# PwrAndBias.net
KiCad netlist of a schematic drawn in Altium Designer
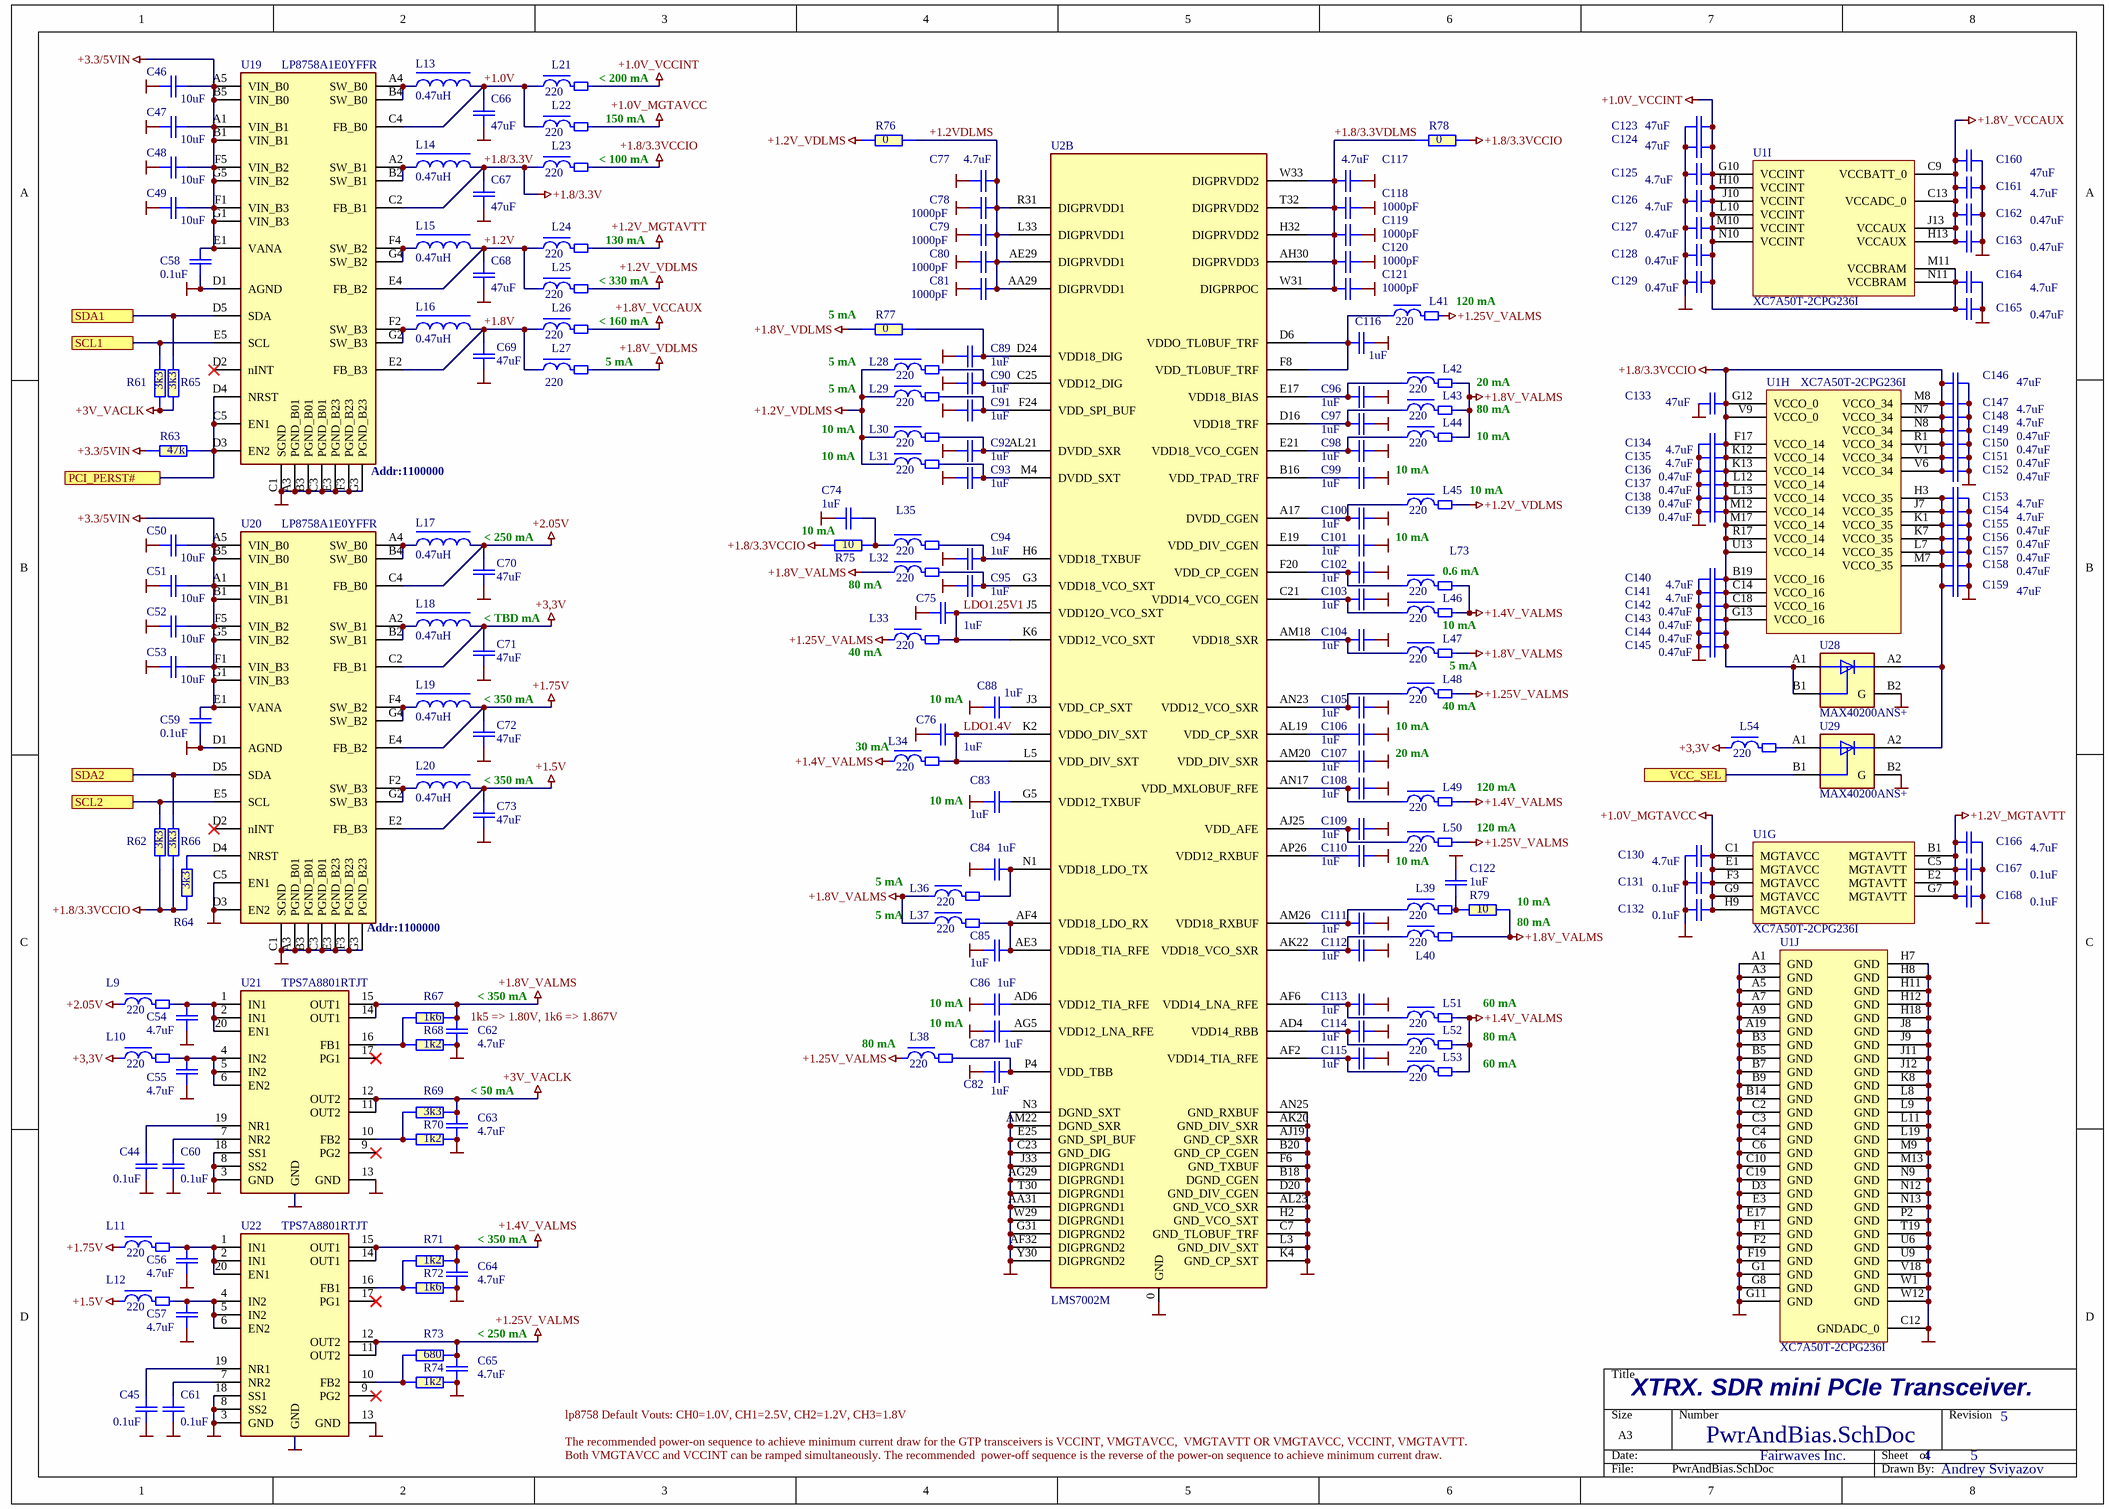
[diagram p0: PwrAndBias.SchDoc]

(export (version "E")
  (design (tool "Eeschema 10.0.6"))
  (components
    (comp (ref "C44")
      (value "0.1uF")
      (footprint "C0402-cirq")
      (description "Capacitor")
      (fields (field (name "MANUFACTURER") "Any") (field (name "TOLERANCE") "20%"))
      (libsource (lib "Capacitors") (part "C0402"))
    )
    (comp (ref "C45")
      (value "0.1uF")
      (footprint "C0402-cirq")
      (description "Capacitor")
      (fields (field (name "MANUFACTURER") "Any") (field (name "TOLERANCE") "20%"))
      (libsource (lib "Capacitors") (part "C0402"))
    )
    (comp (ref "C46")
      (value "10uF")
      (footprint "C0603-Phillips")
      (description "Capacitor")
      (fields (field (name "MANUFACTURER") "Any") (field (name "TOLERANCE") "20%"))
      (libsource (lib "Capacitors") (part "C0603"))
    )
    (comp (ref "C47")
      (value "10uF")
      (footprint "C0603-Phillips")
      (description "Capacitor")
      (fields (field (name "MANUFACTURER") "Any") (field (name "TOLERANCE") "20%"))
      (libsource (lib "Capacitors") (part "C0603"))
    )
    (comp (ref "C48")
      (value "10uF")
      (footprint "C0603-Phillips")
      (description "Capacitor")
      (fields (field (name "MANUFACTURER") "Any") (field (name "TOLERANCE") "20%"))
      (libsource (lib "Capacitors") (part "C0603"))
    )
    (comp (ref "C49")
      (value "10uF")
      (footprint "C0603-Phillips")
      (description "Capacitor")
      (fields (field (name "MANUFACTURER") "Any") (field (name "TOLERANCE") "20%"))
      (libsource (lib "Capacitors") (part "C0603"))
    )
    (comp (ref "C50")
      (value "10uF")
      (footprint "C0603-Phillips")
      (description "Capacitor")
      (fields (field (name "MANUFACTURER") "Any") (field (name "TOLERANCE") "20%"))
      (libsource (lib "Capacitors") (part "C0603"))
    )
    (comp (ref "C51")
      (value "10uF")
      (footprint "C0603-Phillips")
      (description "Capacitor")
      (fields (field (name "MANUFACTURER") "Any") (field (name "TOLERANCE") "20%"))
      (libsource (lib "Capacitors") (part "C0603"))
    )
    (comp (ref "C52")
      (value "10uF")
      (footprint "C0603-Phillips")
      (description "Capacitor")
      (fields (field (name "MANUFACTURER") "Any") (field (name "TOLERANCE") "20%"))
      (libsource (lib "Capacitors") (part "C0603"))
    )
    (comp (ref "C53")
      (value "10uF")
      (footprint "C0603-Phillips")
      (description "Capacitor")
      (fields (field (name "MANUFACTURER") "Any") (field (name "TOLERANCE") "20%"))
      (libsource (lib "Capacitors") (part "C0603"))
    )
    (comp (ref "C54")
      (value "4.7uF")
      (footprint "C0402-cirq")
      (description "Capacitor")
      (fields (field (name "MANUFACTURER") "Any") (field (name "TOLERANCE") "20%"))
      (libsource (lib "Capacitors") (part "C0402"))
    )
    (comp (ref "C55")
      (value "4.7uF")
      (footprint "C0402-cirq")
      (description "Capacitor")
      (fields (field (name "MANUFACTURER") "Any") (field (name "TOLERANCE") "20%"))
      (libsource (lib "Capacitors") (part "C0402"))
    )
    (comp (ref "C56")
      (value "4.7uF")
      (footprint "C0402-cirq")
      (description "Capacitor")
      (fields (field (name "MANUFACTURER") "Any") (field (name "TOLERANCE") "20%"))
      (libsource (lib "Capacitors") (part "C0402"))
    )
    (comp (ref "C57")
      (value "4.7uF")
      (footprint "C0402-cirq")
      (description "Capacitor")
      (fields (field (name "MANUFACTURER") "Any") (field (name "TOLERANCE") "20%"))
      (libsource (lib "Capacitors") (part "C0402"))
    )
    (comp (ref "C58")
      (value "0.1uF")
      (footprint "C0402-cirq")
      (description "Capacitor")
      (fields (field (name "MANUFACTURER") "Any") (field (name "TOLERANCE") "20%"))
      (libsource (lib "Capacitors") (part "C0402"))
    )
    (comp (ref "C59")
      (value "0.1uF")
      (footprint "C0402-cirq")
      (description "Capacitor")
      (fields (field (name "MANUFACTURER") "Any") (field (name "TOLERANCE") "20%"))
      (libsource (lib "Capacitors") (part "C0402"))
    )
    (comp (ref "C60")
      (value "0.1uF")
      (footprint "C0402-cirq")
      (description "Capacitor")
      (fields (field (name "MANUFACTURER") "Any") (field (name "TOLERANCE") "20%"))
      (libsource (lib "Capacitors") (part "C0402"))
    )
    (comp (ref "C61")
      (value "0.1uF")
      (footprint "C0402-cirq")
      (description "Capacitor")
      (fields (field (name "MANUFACTURER") "Any") (field (name "TOLERANCE") "20%"))
      (libsource (lib "Capacitors") (part "C0402"))
    )
    (comp (ref "C62")
      (value "4.7uF")
      (footprint "C0402-cirq")
      (description "Capacitor")
      (fields (field (name "MANUFACTURER") "Any") (field (name "TOLERANCE") "20%"))
      (libsource (lib "Capacitors") (part "C0402"))
    )
    (comp (ref "C63")
      (value "4.7uF")
      (footprint "C0402-cirq")
      (description "Capacitor")
      (fields (field (name "MANUFACTURER") "Any") (field (name "TOLERANCE") "20%"))
      (libsource (lib "Capacitors") (part "C0402"))
    )
    (comp (ref "C64")
      (value "4.7uF")
      (footprint "C0402-cirq")
      (description "Capacitor")
      (fields (field (name "MANUFACTURER") "Any") (field (name "TOLERANCE") "20%"))
      (libsource (lib "Capacitors") (part "C0402"))
    )
    (comp (ref "C65")
      (value "4.7uF")
      (footprint "C0402-cirq")
      (description "Capacitor")
      (fields (field (name "MANUFACTURER") "Any") (field (name "TOLERANCE") "20%"))
      (libsource (lib "Capacitors") (part "C0402"))
    )
    (comp (ref "C66")
      (value "47uF")
      (footprint "C0603 tall")
      (description "Capacitor")
      (fields (field (name "MANUFACTURER") "MuRata") (field (name "TOLERANCE") "20%"))
      (libsource (lib "Andy") (part "C0603-TALL"))
    )
    (comp (ref "C67")
      (value "47uF")
      (footprint "C0603 tall")
      (description "Capacitor")
      (fields (field (name "MANUFACTURER") "MuRata") (field (name "TOLERANCE") "20%"))
      (libsource (lib "Andy") (part "C0603-TALL"))
    )
    (comp (ref "C68")
      (value "47uF")
      (footprint "C0603 tall")
      (description "Capacitor")
      (fields (field (name "MANUFACTURER") "MuRata") (field (name "TOLERANCE") "20%"))
      (libsource (lib "Andy") (part "C0603-TALL"))
    )
    (comp (ref "C69")
      (value "47uF")
      (footprint "C0603 tall")
      (description "Capacitor")
      (fields (field (name "MANUFACTURER") "MuRata") (field (name "TOLERANCE") "20%"))
      (libsource (lib "Andy") (part "C0603-TALL"))
    )
    (comp (ref "C70")
      (value "47uF")
      (footprint "C0603 tall")
      (description "Capacitor")
      (fields (field (name "MANUFACTURER") "MuRata") (field (name "TOLERANCE") "20%"))
      (libsource (lib "Andy") (part "C0603-TALL"))
    )
    (comp (ref "C71")
      (value "47uF")
      (footprint "C0603 tall")
      (description "Capacitor")
      (fields (field (name "MANUFACTURER") "MuRata") (field (name "TOLERANCE") "20%"))
      (libsource (lib "Andy") (part "C0603-TALL"))
    )
    (comp (ref "C72")
      (value "47uF")
      (footprint "C0603 tall")
      (description "Capacitor")
      (fields (field (name "MANUFACTURER") "MuRata") (field (name "TOLERANCE") "20%"))
      (libsource (lib "Andy") (part "C0603-TALL"))
    )
    (comp (ref "C73")
      (value "47uF")
      (footprint "C0603 tall")
      (description "Capacitor")
      (fields (field (name "MANUFACTURER") "MuRata") (field (name "TOLERANCE") "20%"))
      (libsource (lib "Andy") (part "C0603-TALL"))
    )
    (comp (ref "C74")
      (value "1uF")
      (footprint "C0402-cirq")
      (description "Capacitor")
      (fields (field (name "MANUFACTURER") "Any") (field (name "TOLERANCE") "20%"))
      (libsource (lib "Capacitors") (part "C0402"))
    )
    (comp (ref "C75")
      (value "1uF")
      (footprint "C0402-cirq")
      (description "Capacitor")
      (fields (field (name "MANUFACTURER") "Any") (field (name "TOLERANCE") "20%"))
      (libsource (lib "Capacitors") (part "C0402"))
    )
    (comp (ref "C76")
      (value "1uF")
      (footprint "C0402-cirq")
      (description "Capacitor")
      (fields (field (name "MANUFACTURER") "Any") (field (name "TOLERANCE") "20%"))
      (libsource (lib "Capacitors") (part "C0402"))
    )
    (comp (ref "C77")
      (value "4.7uF")
      (footprint "C0402-cirq")
      (description "Capacitor")
      (fields (field (name "MANUFACTURER") "Any") (field (name "TOLERANCE") "20%"))
      (libsource (lib "Capacitors") (part "C0402"))
    )
    (comp (ref "C78")
      (value "1000pF")
      (footprint "C0402-cirq")
      (description "Capacitor")
      (fields (field (name "MANUFACTURER") "Any") (field (name "TOLERANCE") "10%"))
      (libsource (lib "Capacitors") (part "C0402"))
    )
    (comp (ref "C79")
      (value "1000pF")
      (footprint "C0402-cirq")
      (description "Capacitor")
      (fields (field (name "MANUFACTURER") "Any") (field (name "TOLERANCE") "10%"))
      (libsource (lib "Capacitors") (part "C0402"))
    )
    (comp (ref "C80")
      (value "1000pF")
      (footprint "C0402-cirq")
      (description "Capacitor")
      (fields (field (name "MANUFACTURER") "Any") (field (name "TOLERANCE") "10%"))
      (libsource (lib "Capacitors") (part "C0402"))
    )
    (comp (ref "C81")
      (value "1000pF")
      (footprint "C0402-cirq")
      (description "Capacitor")
      (fields (field (name "MANUFACTURER") "Any") (field (name "TOLERANCE") "10%"))
      (libsource (lib "Capacitors") (part "C0402"))
    )
    (comp (ref "C82")
      (value "1uF")
      (footprint "C0402-cirq")
      (description "Capacitor")
      (fields (field (name "MANUFACTURER") "Any") (field (name "TOLERANCE") "20%"))
      (libsource (lib "Capacitors") (part "C0402"))
    )
    (comp (ref "C83")
      (value "1uF")
      (footprint "C0402-cirq")
      (description "Capacitor")
      (fields (field (name "MANUFACTURER") "Any") (field (name "TOLERANCE") "20%"))
      (libsource (lib "Capacitors") (part "C0402"))
    )
    (comp (ref "C84")
      (value "1uF")
      (footprint "C0402-cirq")
      (description "Capacitor")
      (fields (field (name "MANUFACTURER") "Any") (field (name "TOLERANCE") "20%"))
      (libsource (lib "Capacitors") (part "C0402"))
    )
    (comp (ref "C85")
      (value "1uF")
      (footprint "C0402-cirq")
      (description "Capacitor")
      (fields (field (name "MANUFACTURER") "Any") (field (name "TOLERANCE") "20%"))
      (libsource (lib "Capacitors") (part "C0402"))
    )
    (comp (ref "C86")
      (value "1uF")
      (footprint "C0402-cirq")
      (description "Capacitor")
      (fields (field (name "MANUFACTURER") "Any") (field (name "TOLERANCE") "20%"))
      (libsource (lib "Capacitors") (part "C0402"))
    )
    (comp (ref "C87")
      (value "1uF")
      (footprint "C0402-cirq")
      (description "Capacitor")
      (fields (field (name "MANUFACTURER") "Any") (field (name "TOLERANCE") "20%"))
      (libsource (lib "Capacitors") (part "C0402"))
    )
    (comp (ref "C88")
      (value "1uF")
      (footprint "C0402-cirq")
      (description "Capacitor")
      (fields (field (name "MANUFACTURER") "Any") (field (name "TOLERANCE") "20%"))
      (libsource (lib "Capacitors") (part "C0402"))
    )
    (comp (ref "C89")
      (value "1uF")
      (footprint "C0402-cirq")
      (description "Capacitor")
      (fields (field (name "MANUFACTURER") "Any") (field (name "TOLERANCE") "20%"))
      (libsource (lib "Capacitors") (part "C0402"))
    )
    (comp (ref "C90")
      (value "1uF")
      (footprint "C0402-cirq")
      (description "Capacitor")
      (fields (field (name "MANUFACTURER") "Any") (field (name "TOLERANCE") "20%"))
      (libsource (lib "Capacitors") (part "C0402"))
    )
    (comp (ref "C91")
      (value "1uF")
      (footprint "C0402-cirq")
      (description "Capacitor")
      (fields (field (name "MANUFACTURER") "Any") (field (name "TOLERANCE") "20%"))
      (libsource (lib "Capacitors") (part "C0402"))
    )
    (comp (ref "C92")
      (value "1uF")
      (footprint "C0402-cirq")
      (description "Capacitor")
      (fields (field (name "MANUFACTURER") "Any") (field (name "TOLERANCE") "20%"))
      (libsource (lib "Capacitors") (part "C0402"))
    )
    (comp (ref "C93")
      (value "1uF")
      (footprint "C0402-cirq")
      (description "Capacitor")
      (fields (field (name "MANUFACTURER") "Any") (field (name "TOLERANCE") "20%"))
      (libsource (lib "Capacitors") (part "C0402"))
    )
    (comp (ref "C94")
      (value "1uF")
      (footprint "C0402-cirq")
      (description "Capacitor")
      (fields (field (name "MANUFACTURER") "Any") (field (name "TOLERANCE") "20%"))
      (libsource (lib "Capacitors") (part "C0402"))
    )
    (comp (ref "C95")
      (value "1uF")
      (footprint "C0402-cirq")
      (description "Capacitor")
      (fields (field (name "MANUFACTURER") "Any") (field (name "TOLERANCE") "20%"))
      (libsource (lib "Capacitors") (part "C0402"))
    )
    (comp (ref "C96")
      (value "1uF")
      (footprint "C0402-cirq")
      (description "Capacitor")
      (fields (field (name "MANUFACTURER") "Any") (field (name "TOLERANCE") "20%"))
      (libsource (lib "Capacitors") (part "C0402"))
    )
    (comp (ref "C97")
      (value "1uF")
      (footprint "C0402-cirq")
      (description "Capacitor")
      (fields (field (name "MANUFACTURER") "Any") (field (name "TOLERANCE") "20%"))
      (libsource (lib "Capacitors") (part "C0402"))
    )
    (comp (ref "C98")
      (value "1uF")
      (footprint "C0402-cirq")
      (description "Capacitor")
      (fields (field (name "MANUFACTURER") "Any") (field (name "TOLERANCE") "20%"))
      (libsource (lib "Capacitors") (part "C0402"))
    )
    (comp (ref "C99")
      (value "1uF")
      (footprint "C0402-cirq")
      (description "Capacitor")
      (fields (field (name "MANUFACTURER") "Any") (field (name "TOLERANCE") "20%"))
      (libsource (lib "Capacitors") (part "C0402"))
    )
    (comp (ref "C100")
      (value "1uF")
      (footprint "C0402-cirq")
      (description "Capacitor")
      (fields (field (name "MANUFACTURER") "Any") (field (name "TOLERANCE") "20%"))
      (libsource (lib "Capacitors") (part "C0402"))
    )
    (comp (ref "C101")
      (value "1uF")
      (footprint "C0402-cirq")
      (description "Capacitor")
      (fields (field (name "MANUFACTURER") "Any") (field (name "TOLERANCE") "20%"))
      (libsource (lib "Capacitors") (part "C0402"))
    )
    (comp (ref "C102")
      (value "1uF")
      (footprint "C0402-cirq")
      (description "Capacitor")
      (fields (field (name "MANUFACTURER") "Any") (field (name "TOLERANCE") "20%"))
      (libsource (lib "Capacitors") (part "C0402"))
    )
    (comp (ref "C103")
      (value "1uF")
      (footprint "C0402-cirq")
      (description "Capacitor")
      (fields (field (name "MANUFACTURER") "Any") (field (name "TOLERANCE") "20%"))
      (libsource (lib "Capacitors") (part "C0402"))
    )
    (comp (ref "C104")
      (value "1uF")
      (footprint "C0402-cirq")
      (description "Capacitor")
      (fields (field (name "MANUFACTURER") "Any") (field (name "TOLERANCE") "20%"))
      (libsource (lib "Capacitors") (part "C0402"))
    )
    (comp (ref "C105")
      (value "1uF")
      (footprint "C0402-cirq")
      (description "Capacitor")
      (fields (field (name "MANUFACTURER") "Any") (field (name "TOLERANCE") "20%"))
      (libsource (lib "Capacitors") (part "C0402"))
    )
    (comp (ref "C106")
      (value "1uF")
      (footprint "C0402-cirq")
      (description "Capacitor")
      (fields (field (name "MANUFACTURER") "Any") (field (name "TOLERANCE") "20%"))
      (libsource (lib "Capacitors") (part "C0402"))
    )
    (comp (ref "C107")
      (value "1uF")
      (footprint "C0402-cirq")
      (description "Capacitor")
      (fields (field (name "MANUFACTURER") "Any") (field (name "TOLERANCE") "20%"))
      (libsource (lib "Capacitors") (part "C0402"))
    )
    (comp (ref "C108")
      (value "1uF")
      (footprint "C0402-cirq")
      (description "Capacitor")
      (fields (field (name "MANUFACTURER") "Any") (field (name "TOLERANCE") "20%"))
      (libsource (lib "Capacitors") (part "C0402"))
    )
    (comp (ref "C109")
      (value "1uF")
      (footprint "C0402-cirq")
      (description "Capacitor")
      (fields (field (name "MANUFACTURER") "Any") (field (name "TOLERANCE") "20%"))
      (libsource (lib "Capacitors") (part "C0402"))
    )
    (comp (ref "C110")
      (value "1uF")
      (footprint "C0402-cirq")
      (description "Capacitor")
      (fields (field (name "MANUFACTURER") "Any") (field (name "TOLERANCE") "20%"))
      (libsource (lib "Capacitors") (part "C0402"))
    )
    (comp (ref "C111")
      (value "1uF")
      (footprint "C0402-cirq")
      (description "Capacitor")
      (fields (field (name "MANUFACTURER") "Any") (field (name "TOLERANCE") "20%"))
      (libsource (lib "Capacitors") (part "C0402"))
    )
    (comp (ref "C112")
      (value "1uF")
      (footprint "C0402-cirq")
      (description "Capacitor")
      (fields (field (name "MANUFACTURER") "Any") (field (name "TOLERANCE") "20%"))
      (libsource (lib "Capacitors") (part "C0402"))
    )
    (comp (ref "C113")
      (value "1uF")
      (footprint "C0402-cirq")
      (description "Capacitor")
      (fields (field (name "MANUFACTURER") "Any") (field (name "TOLERANCE") "20%"))
      (libsource (lib "Capacitors") (part "C0402"))
    )
    (comp (ref "C114")
      (value "1uF")
      (footprint "C0402-cirq")
      (description "Capacitor")
      (fields (field (name "MANUFACTURER") "Any") (field (name "TOLERANCE") "20%"))
      (libsource (lib "Capacitors") (part "C0402"))
    )
    (comp (ref "C115")
      (value "1uF")
      (footprint "C0402-cirq")
      (description "Capacitor")
      (fields (field (name "MANUFACTURER") "Any") (field (name "TOLERANCE") "20%"))
      (libsource (lib "Capacitors") (part "C0402"))
    )
    (comp (ref "C116")
      (value "1uF")
      (footprint "C0402-cirq")
      (description "Capacitor")
      (fields (field (name "MANUFACTURER") "Any") (field (name "TOLERANCE") "20%"))
      (libsource (lib "Capacitors") (part "C0402"))
    )
    (comp (ref "C117")
      (value "4.7uF")
      (footprint "C0402-cirq")
      (description "Capacitor")
      (fields (field (name "MANUFACTURER") "Any") (field (name "TOLERANCE") "20%"))
      (libsource (lib "Capacitors") (part "C0402"))
    )
    (comp (ref "C118")
      (value "1000pF")
      (footprint "C0402-cirq")
      (description "Capacitor")
      (fields (field (name "MANUFACTURER") "Any") (field (name "TOLERANCE") "10%"))
      (libsource (lib "Capacitors") (part "C0402"))
    )
    (comp (ref "C119")
      (value "1000pF")
      (footprint "C0402-cirq")
      (description "Capacitor")
      (fields (field (name "MANUFACTURER") "Any") (field (name "TOLERANCE") "10%"))
      (libsource (lib "Capacitors") (part "C0402"))
    )
    (comp (ref "C120")
      (value "1000pF")
      (footprint "C0402-cirq")
      (description "Capacitor")
      (fields (field (name "MANUFACTURER") "Any") (field (name "TOLERANCE") "10%"))
      (libsource (lib "Capacitors") (part "C0402"))
    )
    (comp (ref "C121")
      (value "1000pF")
      (footprint "C0402-cirq")
      (description "Capacitor")
      (fields (field (name "MANUFACTURER") "Any") (field (name "TOLERANCE") "10%"))
      (libsource (lib "Capacitors") (part "C0402"))
    )
    (comp (ref "C122")
      (value "1uF")
      (footprint "C0402-cirq")
      (description "Capacitor")
      (fields (field (name "MANUFACTURER") "Any") (field (name "TOLERANCE") "20%"))
      (libsource (lib "Capacitors") (part "C0402"))
    )
    (comp (ref "C123")
      (value "47uF")
      (footprint "C0603 tall")
      (description "Capacitor")
      (fields (field (name "MANUFACTURER") "MuRata") (field (name "TOLERANCE") "20%"))
      (libsource (lib "Andy") (part "C0603-TALL"))
    )
    (comp (ref "C124")
      (value "47uF")
      (footprint "C0603 tall")
      (description "Capacitor")
      (fields (field (name "MANUFACTURER") "MuRata") (field (name "TOLERANCE") "20%"))
      (libsource (lib "Andy") (part "C0603-TALL"))
    )
    (comp (ref "C125")
      (value "4.7uF")
      (footprint "C0402-cirq")
      (description "Capacitor")
      (fields (field (name "MANUFACTURER") "Any") (field (name "TOLERANCE") "20%"))
      (libsource (lib "Capacitors") (part "C0402"))
    )
    (comp (ref "C126")
      (value "4.7uF")
      (footprint "C0402-cirq")
      (description "Capacitor")
      (fields (field (name "MANUFACTURER") "Any") (field (name "TOLERANCE") "20%"))
      (libsource (lib "Capacitors") (part "C0402"))
    )
    (comp (ref "C127")
      (value "0.47uF")
      (footprint "C0402-cirq")
      (description "Capacitor")
      (fields (field (name "MANUFACTURER") "Any") (field (name "TOLERANCE") "20%"))
      (libsource (lib "Capacitors") (part "C0402"))
    )
    (comp (ref "C128")
      (value "0.47uF")
      (footprint "C0402-cirq")
      (description "Capacitor")
      (fields (field (name "MANUFACTURER") "Any") (field (name "TOLERANCE") "20%"))
      (libsource (lib "Capacitors") (part "C0402"))
    )
    (comp (ref "C129")
      (value "0.47uF")
      (footprint "C0402-cirq")
      (description "Capacitor")
      (fields (field (name "MANUFACTURER") "Any") (field (name "TOLERANCE") "20%"))
      (libsource (lib "Capacitors") (part "C0402"))
    )
    (comp (ref "C130")
      (value "4.7uF")
      (footprint "C0402-cirq")
      (description "Capacitor")
      (fields (field (name "MANUFACTURER") "Any") (field (name "TOLERANCE") "20%"))
      (libsource (lib "Capacitors") (part "C0402"))
    )
    (comp (ref "C131")
      (value "0.1uF")
      (footprint "C0402-cirq")
      (description "Capacitor")
      (fields (field (name "MANUFACTURER") "Any") (field (name "TOLERANCE") "20%"))
      (libsource (lib "Capacitors") (part "C0402"))
    )
    (comp (ref "C132")
      (value "0.1uF")
      (footprint "C0402-cirq")
      (description "Capacitor")
      (fields (field (name "MANUFACTURER") "Any") (field (name "TOLERANCE") "20%"))
      (libsource (lib "Capacitors") (part "C0402"))
    )
    (comp (ref "C133")
      (value "47uF")
      (footprint "C0603 tall")
      (description "Capacitor")
      (fields (field (name "MANUFACTURER") "MuRata") (field (name "TOLERANCE") "20%"))
      (libsource (lib "Andy") (part "C0603-TALL"))
    )
    (comp (ref "C134")
      (value "4.7uF")
      (footprint "C0402-cirq")
      (description "Capacitor")
      (fields (field (name "MANUFACTURER") "Any") (field (name "TOLERANCE") "20%"))
      (libsource (lib "Capacitors") (part "C0402"))
    )
    (comp (ref "C135")
      (value "4.7uF")
      (footprint "C0402-cirq")
      (description "Capacitor")
      (fields (field (name "MANUFACTURER") "Any") (field (name "TOLERANCE") "20%"))
      (libsource (lib "Capacitors") (part "C0402"))
    )
    (comp (ref "C136")
      (value "0.47uF")
      (footprint "C0402-cirq")
      (description "Capacitor")
      (fields (field (name "MANUFACTURER") "Any") (field (name "TOLERANCE") "20%"))
      (libsource (lib "Capacitors") (part "C0402"))
    )
    (comp (ref "C137")
      (value "0.47uF")
      (footprint "C0402-cirq")
      (description "Capacitor")
      (fields (field (name "MANUFACTURER") "Any") (field (name "TOLERANCE") "20%"))
      (libsource (lib "Capacitors") (part "C0402"))
    )
    (comp (ref "C138")
      (value "0.47uF")
      (footprint "C0402-cirq")
      (description "Capacitor")
      (fields (field (name "MANUFACTURER") "Any") (field (name "TOLERANCE") "20%"))
      (libsource (lib "Capacitors") (part "C0402"))
    )
    (comp (ref "C139")
      (value "0.47uF")
      (footprint "C0402-cirq")
      (description "Capacitor")
      (fields (field (name "MANUFACTURER") "Any") (field (name "TOLERANCE") "20%"))
      (libsource (lib "Capacitors") (part "C0402"))
    )
    (comp (ref "C140")
      (value "4.7uF")
      (footprint "C0402-cirq")
      (description "Capacitor")
      (fields (field (name "MANUFACTURER") "Any") (field (name "TOLERANCE") "20%"))
      (libsource (lib "Capacitors") (part "C0402"))
    )
    (comp (ref "C141")
      (value "4.7uF")
      (footprint "C0402-cirq")
      (description "Capacitor")
      (fields (field (name "MANUFACTURER") "Any") (field (name "TOLERANCE") "20%"))
      (libsource (lib "Capacitors") (part "C0402"))
    )
    (comp (ref "C142")
      (value "0.47uF")
      (footprint "C0402-cirq")
      (description "Capacitor")
      (fields (field (name "MANUFACTURER") "Any") (field (name "TOLERANCE") "20%"))
      (libsource (lib "Capacitors") (part "C0402"))
    )
    (comp (ref "C143")
      (value "0.47uF")
      (footprint "C0402-cirq")
      (description "Capacitor")
      (fields (field (name "MANUFACTURER") "Any") (field (name "TOLERANCE") "20%"))
      (libsource (lib "Capacitors") (part "C0402"))
    )
    (comp (ref "C144")
      (value "0.47uF")
      (footprint "C0402-cirq")
      (description "Capacitor")
      (fields (field (name "MANUFACTURER") "Any") (field (name "TOLERANCE") "20%"))
      (libsource (lib "Capacitors") (part "C0402"))
    )
    (comp (ref "C145")
      (value "0.47uF")
      (footprint "C0402-cirq")
      (description "Capacitor")
      (fields (field (name "MANUFACTURER") "Any") (field (name "TOLERANCE") "20%"))
      (libsource (lib "Capacitors") (part "C0402"))
    )
    (comp (ref "C146")
      (value "47uF")
      (footprint "C0603 tall")
      (description "Capacitor")
      (fields (field (name "MANUFACTURER") "MuRata") (field (name "TOLERANCE") "20%"))
      (libsource (lib "Andy") (part "C0603-TALL"))
    )
    (comp (ref "C147")
      (value "4.7uF")
      (footprint "C0402-cirq")
      (description "Capacitor")
      (fields (field (name "MANUFACTURER") "Any") (field (name "TOLERANCE") "20%"))
      (libsource (lib "Capacitors") (part "C0402"))
    )
    (comp (ref "C148")
      (value "4.7uF")
      (footprint "C0402-cirq")
      (description "Capacitor")
      (fields (field (name "MANUFACTURER") "Any") (field (name "TOLERANCE") "20%"))
      (libsource (lib "Capacitors") (part "C0402"))
    )
    (comp (ref "C149")
      (value "0.47uF")
      (footprint "C0402-cirq")
      (description "Capacitor")
      (fields (field (name "MANUFACTURER") "Any") (field (name "TOLERANCE") "20%"))
      (libsource (lib "Capacitors") (part "C0402"))
    )
    (comp (ref "C150")
      (value "0.47uF")
      (footprint "C0402-cirq")
      (description "Capacitor")
      (fields (field (name "MANUFACTURER") "Any") (field (name "TOLERANCE") "20%"))
      (libsource (lib "Capacitors") (part "C0402"))
    )
    (comp (ref "C151")
      (value "0.47uF")
      (footprint "C0402-cirq")
      (description "Capacitor")
      (fields (field (name "MANUFACTURER") "Any") (field (name "TOLERANCE") "20%"))
      (libsource (lib "Capacitors") (part "C0402"))
    )
    (comp (ref "C152")
      (value "0.47uF")
      (footprint "C0402-cirq")
      (description "Capacitor")
      (fields (field (name "MANUFACTURER") "Any") (field (name "TOLERANCE") "20%"))
      (libsource (lib "Capacitors") (part "C0402"))
    )
    (comp (ref "C153")
      (value "4.7uF")
      (footprint "C0402-cirq")
      (description "Capacitor")
      (fields (field (name "MANUFACTURER") "Any") (field (name "TOLERANCE") "20%"))
      (libsource (lib "Capacitors") (part "C0402"))
    )
    (comp (ref "C154")
      (value "4.7uF")
      (footprint "C0402-cirq")
      (description "Capacitor")
      (fields (field (name "MANUFACTURER") "Any") (field (name "TOLERANCE") "20%"))
      (libsource (lib "Capacitors") (part "C0402"))
    )
    (comp (ref "C155")
      (value "0.47uF")
      (footprint "C0402-cirq")
      (description "Capacitor")
      (fields (field (name "MANUFACTURER") "Any") (field (name "TOLERANCE") "20%"))
      (libsource (lib "Capacitors") (part "C0402"))
    )
    (comp (ref "C156")
      (value "0.47uF")
      (footprint "C0402-cirq")
      (description "Capacitor")
      (fields (field (name "MANUFACTURER") "Any") (field (name "TOLERANCE") "20%"))
      (libsource (lib "Capacitors") (part "C0402"))
    )
    (comp (ref "C157")
      (value "0.47uF")
      (footprint "C0402-cirq")
      (description "Capacitor")
      (fields (field (name "MANUFACTURER") "Any") (field (name "TOLERANCE") "20%"))
      (libsource (lib "Capacitors") (part "C0402"))
    )
    (comp (ref "C158")
      (value "0.47uF")
      (footprint "C0402-cirq")
      (description "Capacitor")
      (fields (field (name "MANUFACTURER") "Any") (field (name "TOLERANCE") "20%"))
      (libsource (lib "Capacitors") (part "C0402"))
    )
    (comp (ref "C159")
      (value "47uF")
      (footprint "C0603 tall")
      (description "Capacitor")
      (fields (field (name "MANUFACTURER") "MuRata") (field (name "TOLERANCE") "20%"))
      (libsource (lib "Andy") (part "C0603-TALL"))
    )
    (comp (ref "C160")
      (value "47uF")
      (footprint "C0603 tall")
      (description "Capacitor")
      (fields (field (name "MANUFACTURER") "MuRata") (field (name "TOLERANCE") "20%"))
      (libsource (lib "Andy") (part "C0603-TALL"))
    )
    (comp (ref "C161")
      (value "4.7uF")
      (footprint "C0402-cirq")
      (description "Capacitor")
      (fields (field (name "MANUFACTURER") "Any") (field (name "TOLERANCE") "20%"))
      (libsource (lib "Capacitors") (part "C0402"))
    )
    (comp (ref "C162")
      (value "0.47uF")
      (footprint "C0402-cirq")
      (description "Capacitor")
      (fields (field (name "MANUFACTURER") "Any") (field (name "TOLERANCE") "20%"))
      (libsource (lib "Capacitors") (part "C0402"))
    )
    (comp (ref "C163")
      (value "0.47uF")
      (footprint "C0402-cirq")
      (description "Capacitor")
      (fields (field (name "MANUFACTURER") "Any") (field (name "TOLERANCE") "20%"))
      (libsource (lib "Capacitors") (part "C0402"))
    )
    (comp (ref "C164")
      (value "4.7uF")
      (footprint "C0402-cirq")
      (description "Capacitor")
      (fields (field (name "MANUFACTURER") "Any") (field (name "TOLERANCE") "20%"))
      (libsource (lib "Capacitors") (part "C0402"))
    )
    (comp (ref "C165")
      (value "0.47uF")
      (footprint "C0402-cirq")
      (description "Capacitor")
      (fields (field (name "MANUFACTURER") "Any") (field (name "TOLERANCE") "20%"))
      (libsource (lib "Capacitors") (part "C0402"))
    )
    (comp (ref "C166")
      (value "4.7uF")
      (footprint "C0402-cirq")
      (description "Capacitor")
      (fields (field (name "MANUFACTURER") "Any") (field (name "TOLERANCE") "20%"))
      (libsource (lib "Capacitors") (part "C0402"))
    )
    (comp (ref "C167")
      (value "0.1uF")
      (footprint "C0402-cirq")
      (description "Capacitor")
      (fields (field (name "MANUFACTURER") "Any") (field (name "TOLERANCE") "20%"))
      (libsource (lib "Capacitors") (part "C0402"))
    )
    (comp (ref "C168")
      (value "0.1uF")
      (footprint "C0402-cirq")
      (description "Capacitor")
      (fields (field (name "MANUFACTURER") "Any") (field (name "TOLERANCE") "20%"))
      (libsource (lib "Capacitors") (part "C0402"))
    )
    (comp (ref "L9")
      (value "220")
      (footprint "BEAD0402-Phillips")
      (description "Ferrite bead EMIFIL")
      (fields (field (name "MANUFACTURER") "MURATA"))
      (libsource (lib "Andy") (part "EMI BLM15"))
    )
    (comp (ref "L10")
      (value "220")
      (footprint "BEAD0402-Phillips")
      (description "Ferrite bead EMIFIL")
      (fields (field (name "MANUFACTURER") "MURATA"))
      (libsource (lib "Andy") (part "EMI BLM15"))
    )
    (comp (ref "L11")
      (value "220")
      (footprint "BEAD0402-Phillips")
      (description "Ferrite bead EMIFIL")
      (fields (field (name "MANUFACTURER") "MURATA"))
      (libsource (lib "Andy") (part "EMI BLM15"))
    )
    (comp (ref "L12")
      (value "220")
      (footprint "BEAD0402-Phillips")
      (description "Ferrite bead EMIFIL")
      (fields (field (name "MANUFACTURER") "MURATA"))
      (libsource (lib "Andy") (part "EMI BLM15"))
    )
    (comp (ref "L13")
      (value "0.47uH")
      (footprint "L-VLS201610HBX")
      (description "Coil")
      (fields (field (name "MANUFACTURER") "TDK"))
      (libsource (lib "Andy") (part "L-VLS20161xHBX-1"))
    )
    (comp (ref "L14")
      (value "0.47uH")
      (footprint "L-VLS201610HBX")
      (description "Coil")
      (fields (field (name "MANUFACTURER") "TDK"))
      (libsource (lib "Andy") (part "L-VLS20161xHBX-1"))
    )
    (comp (ref "L15")
      (value "0.47uH")
      (footprint "L-VLS201610HBX")
      (description "Coil")
      (fields (field (name "MANUFACTURER") "TDK"))
      (libsource (lib "Andy") (part "L-VLS20161xHBX-1"))
    )
    (comp (ref "L16")
      (value "0.47uH")
      (footprint "L-VLS201610HBX")
      (description "Coil")
      (fields (field (name "MANUFACTURER") "TDK"))
      (libsource (lib "Andy") (part "L-VLS20161xHBX-1"))
    )
    (comp (ref "L17")
      (value "0.47uH")
      (footprint "L-VLS201610HBX")
      (description "Coil")
      (fields (field (name "MANUFACTURER") "TDK"))
      (libsource (lib "Andy") (part "L-VLS20161xHBX-1"))
    )
    (comp (ref "L18")
      (value "0.47uH")
      (footprint "L-VLS201610HBX")
      (description "Coil")
      (fields (field (name "MANUFACTURER") "TDK"))
      (libsource (lib "Andy") (part "L-VLS20161xHBX-1"))
    )
    (comp (ref "L19")
      (value "0.47uH")
      (footprint "L-VLS201610HBX")
      (description "Coil")
      (fields (field (name "MANUFACTURER") "TDK"))
      (libsource (lib "Andy") (part "L-VLS20161xHBX-1"))
    )
    (comp (ref "L20")
      (value "0.47uH")
      (footprint "L-VLS201610HBX")
      (description "Coil")
      (fields (field (name "MANUFACTURER") "TDK"))
      (libsource (lib "Andy") (part "L-VLS20161xHBX-1"))
    )
    (comp (ref "L21")
      (value "220")
      (footprint "BEAD0402-Phillips")
      (description "Ferrite bead EMIFIL")
      (fields (field (name "MANUFACTURER") "MURATA"))
      (libsource (lib "Andy") (part "EMI BLM15"))
    )
    (comp (ref "L22")
      (value "220")
      (footprint "BEAD0402-Phillips")
      (description "Ferrite bead EMIFIL")
      (fields (field (name "MANUFACTURER") "MURATA"))
      (libsource (lib "Andy") (part "EMI BLM15"))
    )
    (comp (ref "L23")
      (value "220")
      (footprint "BEAD0402-Phillips")
      (description "Ferrite bead EMIFIL")
      (fields (field (name "MANUFACTURER") "MURATA"))
      (libsource (lib "Andy") (part "EMI BLM15"))
    )
    (comp (ref "L24")
      (value "220")
      (footprint "BEAD0402-Phillips")
      (description "Ferrite bead EMIFIL")
      (fields (field (name "MANUFACTURER") "MURATA"))
      (libsource (lib "Andy") (part "EMI BLM15"))
    )
    (comp (ref "L25")
      (value "220")
      (footprint "BEAD0402-Phillips")
      (description "Ferrite bead EMIFIL")
      (fields (field (name "MANUFACTURER") "MURATA"))
      (libsource (lib "Andy") (part "EMI BLM15"))
    )
    (comp (ref "L26")
      (value "220")
      (footprint "BEAD0402-Phillips")
      (description "Ferrite bead EMIFIL")
      (fields (field (name "MANUFACTURER") "MURATA"))
      (libsource (lib "Andy") (part "EMI BLM15"))
    )
    (comp (ref "L27")
      (value "220")
      (footprint "BEAD0402-Phillips")
      (description "Ferrite bead EMIFIL")
      (fields (field (name "MANUFACTURER") "MURATA"))
      (libsource (lib "Andy") (part "EMI BLM15"))
    )
    (comp (ref "L28")
      (value "220")
      (footprint "BEAD0402-Phillips")
      (description "Ferrite bead EMIFIL")
      (fields (field (name "MANUFACTURER") "MURATA"))
      (libsource (lib "Andy") (part "EMI BLM15"))
    )
    (comp (ref "L29")
      (value "220")
      (footprint "BEAD0402-Phillips")
      (description "Ferrite bead EMIFIL")
      (fields (field (name "MANUFACTURER") "MURATA"))
      (libsource (lib "Andy") (part "EMI BLM15"))
    )
    (comp (ref "L30")
      (value "220")
      (footprint "BEAD0402-Phillips")
      (description "Ferrite bead EMIFIL")
      (fields (field (name "MANUFACTURER") "MURATA"))
      (libsource (lib "Andy") (part "EMI BLM15"))
    )
    (comp (ref "L31")
      (value "220")
      (footprint "BEAD0402-Phillips")
      (description "Ferrite bead EMIFIL")
      (fields (field (name "MANUFACTURER") "MURATA"))
      (libsource (lib "Andy") (part "EMI BLM15"))
    )
    (comp (ref "L32")
      (value "220")
      (footprint "BEAD0402-Phillips")
      (description "Ferrite bead EMIFIL")
      (fields (field (name "MANUFACTURER") "MURATA"))
      (libsource (lib "Andy") (part "EMI BLM15"))
    )
    (comp (ref "L33")
      (value "220")
      (footprint "BEAD0402-Phillips")
      (description "Ferrite bead EMIFIL")
      (fields (field (name "MANUFACTURER") "MURATA"))
      (libsource (lib "Andy") (part "EMI BLM15"))
    )
    (comp (ref "L34")
      (value "220")
      (footprint "BEAD0402-Phillips")
      (description "Ferrite bead EMIFIL")
      (fields (field (name "MANUFACTURER") "MURATA"))
      (libsource (lib "Andy") (part "EMI BLM15"))
    )
    (comp (ref "L35")
      (value "220")
      (footprint "BEAD0402-Phillips")
      (description "Ferrite bead EMIFIL")
      (fields (field (name "MANUFACTURER") "MURATA"))
      (libsource (lib "Andy") (part "EMI BLM15"))
    )
    (comp (ref "L36")
      (value "220")
      (footprint "BEAD0402-Phillips")
      (description "Ferrite bead EMIFIL")
      (fields (field (name "MANUFACTURER") "MURATA"))
      (libsource (lib "Andy") (part "EMI BLM15"))
    )
    (comp (ref "L37")
      (value "220")
      (footprint "BEAD0402-Phillips")
      (description "Ferrite bead EMIFIL")
      (fields (field (name "MANUFACTURER") "MURATA"))
      (libsource (lib "Andy") (part "EMI BLM15"))
    )
    (comp (ref "L38")
      (value "220")
      (footprint "BEAD0402-Phillips")
      (description "Ferrite bead EMIFIL")
      (fields (field (name "MANUFACTURER") "MURATA"))
      (libsource (lib "Andy") (part "EMI BLM15"))
    )
    (comp (ref "L39")
      (value "220")
      (footprint "BEAD0402-Phillips")
      (description "Ferrite bead EMIFIL")
      (fields (field (name "MANUFACTURER") "MURATA"))
      (libsource (lib "Andy") (part "EMI BLM15"))
    )
    (comp (ref "L40")
      (value "220")
      (footprint "BEAD0402-Phillips")
      (description "Ferrite bead EMIFIL")
      (fields (field (name "MANUFACTURER") "MURATA"))
      (libsource (lib "Andy") (part "EMI BLM15"))
    )
    (comp (ref "L41")
      (value "220")
      (footprint "BEAD0402-Phillips")
      (description "Ferrite bead EMIFIL")
      (fields (field (name "MANUFACTURER") "MURATA"))
      (libsource (lib "Andy") (part "EMI BLM15"))
    )
    (comp (ref "L42")
      (value "220")
      (footprint "BEAD0402-Phillips")
      (description "Ferrite bead EMIFIL")
      (fields (field (name "MANUFACTURER") "MURATA"))
      (libsource (lib "Andy") (part "EMI BLM15"))
    )
    (comp (ref "L43")
      (value "220")
      (footprint "BEAD0402-Phillips")
      (description "Ferrite bead EMIFIL")
      (fields (field (name "MANUFACTURER") "MURATA"))
      (libsource (lib "Andy") (part "EMI BLM15"))
    )
    (comp (ref "L44")
      (value "220")
      (footprint "BEAD0402-Phillips")
      (description "Ferrite bead EMIFIL")
      (fields (field (name "MANUFACTURER") "MURATA"))
      (libsource (lib "Andy") (part "EMI BLM15"))
    )
    (comp (ref "L45")
      (value "220")
      (footprint "BEAD0402-Phillips")
      (description "Ferrite bead EMIFIL")
      (fields (field (name "MANUFACTURER") "MURATA"))
      (libsource (lib "Andy") (part "EMI BLM15"))
    )
    (comp (ref "L46")
      (value "220")
      (footprint "BEAD0402-Phillips")
      (description "Ferrite bead EMIFIL")
      (fields (field (name "MANUFACTURER") "MURATA"))
      (libsource (lib "Andy") (part "EMI BLM15"))
    )
    (comp (ref "L47")
      (value "220")
      (footprint "BEAD0402-Phillips")
      (description "Ferrite bead EMIFIL")
      (fields (field (name "MANUFACTURER") "MURATA"))
      (libsource (lib "Andy") (part "EMI BLM15"))
    )
    (comp (ref "L48")
      (value "220")
      (footprint "BEAD0402-Phillips")
      (description "Ferrite bead EMIFIL")
      (fields (field (name "MANUFACTURER") "MURATA"))
      (libsource (lib "Andy") (part "EMI BLM15"))
    )
    (comp (ref "L49")
      (value "220")
      (footprint "BEAD0402-Phillips")
      (description "Ferrite bead EMIFIL")
      (fields (field (name "MANUFACTURER") "MURATA"))
      (libsource (lib "Andy") (part "EMI BLM15"))
    )
    (comp (ref "L50")
      (value "220")
      (footprint "BEAD0402-Phillips")
      (description "Ferrite bead EMIFIL")
      (fields (field (name "MANUFACTURER") "MURATA"))
      (libsource (lib "Andy") (part "EMI BLM15"))
    )
    (comp (ref "L51")
      (value "220")
      (footprint "BEAD0402-Phillips")
      (description "Ferrite bead EMIFIL")
      (fields (field (name "MANUFACTURER") "MURATA"))
      (libsource (lib "Andy") (part "EMI BLM15"))
    )
    (comp (ref "L52")
      (value "220")
      (footprint "BEAD0402-Phillips")
      (description "Ferrite bead EMIFIL")
      (fields (field (name "MANUFACTURER") "MURATA"))
      (libsource (lib "Andy") (part "EMI BLM15"))
    )
    (comp (ref "L53")
      (value "220")
      (footprint "BEAD0402-Phillips")
      (description "Ferrite bead EMIFIL")
      (fields (field (name "MANUFACTURER") "MURATA"))
      (libsource (lib "Andy") (part "EMI BLM15"))
    )
    (comp (ref "L54")
      (value "220")
      (footprint "BEAD0402-Phillips")
      (description "Ferrite bead EMIFIL")
      (fields (field (name "MANUFACTURER") "MURATA"))
      (libsource (lib "Andy") (part "EMI BLM15"))
    )
    (comp (ref "L73")
      (value "220")
      (footprint "BEAD0402-Phillips")
      (description "Ferrite bead EMIFIL")
      (fields (field (name "MANUFACTURER") "MURATA"))
      (libsource (lib "Andy") (part "EMI BLM15"))
    )
    (comp (ref "R61")
      (value "3k3")
      (footprint "R0402-Phillips")
      (description "Resistor")
      (fields (field (name "MANUFACTURER") "BOURNS") (field (name "TOLERANCE") "5%"))
      (libsource (lib "Andy") (part "R0402"))
    )
    (comp (ref "R62")
      (value "3k3")
      (footprint "R0402-Phillips")
      (description "Resistor")
      (fields (field (name "MANUFACTURER") "BOURNS") (field (name "TOLERANCE") "5%"))
      (libsource (lib "Andy") (part "R0402"))
    )
    (comp (ref "R63")
      (value "47k")
      (footprint "R0402-Phillips")
      (description "Resistor")
      (fields (field (name "MANUFACTURER") "BOURNS") (field (name "TOLERANCE") "5%"))
      (libsource (lib "") (part "R0402_1"))
    )
    (comp (ref "R64")
      (value "3k3")
      (footprint "R0402-Phillips")
      (description "Resistor")
      (fields (field (name "MANUFACTURER") "BOURNS") (field (name "TOLERANCE") "5%"))
      (libsource (lib "Andy") (part "R0402"))
    )
    (comp (ref "R65")
      (value "3k3")
      (footprint "R0402-Phillips")
      (description "Resistor")
      (fields (field (name "MANUFACTURER") "BOURNS") (field (name "TOLERANCE") "5%"))
      (libsource (lib "Andy") (part "R0402"))
    )
    (comp (ref "R66")
      (value "3k3")
      (footprint "R0402-Phillips")
      (description "Resistor")
      (fields (field (name "MANUFACTURER") "BOURNS") (field (name "TOLERANCE") "5%"))
      (libsource (lib "Andy") (part "R0402"))
    )
    (comp (ref "R67")
      (value "1k6")
      (footprint "R0402-Phillips")
      (description "Resistor")
      (fields (field (name "MANUFACTURER") "BOURNS") (field (name "TOLERANCE") "5%"))
      (libsource (lib "") (part "R0402_1"))
    )
    (comp (ref "R68")
      (value "1k2")
      (footprint "R0402-Phillips")
      (description "Resistor")
      (fields (field (name "MANUFACTURER") "BOURNS") (field (name "TOLERANCE") "5%"))
      (libsource (lib "") (part "R0402_1"))
    )
    (comp (ref "R69")
      (value "3k3")
      (footprint "R0402-Phillips")
      (description "Resistor")
      (fields (field (name "MANUFACTURER") "BOURNS") (field (name "TOLERANCE") "5%"))
      (libsource (lib "") (part "R0402_1"))
    )
    (comp (ref "R70")
      (value "1k2")
      (footprint "R0402-Phillips")
      (description "Resistor")
      (fields (field (name "MANUFACTURER") "BOURNS") (field (name "TOLERANCE") "5%"))
      (libsource (lib "") (part "R0402_1"))
    )
    (comp (ref "R71")
      (value "1k2")
      (footprint "R0402-Phillips")
      (description "Resistor")
      (fields (field (name "MANUFACTURER") "BOURNS") (field (name "TOLERANCE") "5%"))
      (libsource (lib "") (part "R0402_1"))
    )
    (comp (ref "R72")
      (value "1k6")
      (footprint "R0402-Phillips")
      (description "Resistor")
      (fields (field (name "MANUFACTURER") "BOURNS") (field (name "TOLERANCE") "5%"))
      (libsource (lib "") (part "R0402_1"))
    )
    (comp (ref "R73")
      (value "680")
      (footprint "R0402-Phillips")
      (description "Resistor")
      (fields (field (name "MANUFACTURER") "BOURNS") (field (name "TOLERANCE") "5%"))
      (libsource (lib "") (part "R0402_1"))
    )
    (comp (ref "R74")
      (value "1k2")
      (footprint "R0402-Phillips")
      (description "Resistor")
      (fields (field (name "MANUFACTURER") "BOURNS") (field (name "TOLERANCE") "5%"))
      (libsource (lib "") (part "R0402_1"))
    )
    (comp (ref "R75")
      (value "10")
      (footprint "R0402-Phillips")
      (description "Resistor")
      (fields (field (name "MANUFACTURER") "BOURNS") (field (name "TOLERANCE") "5%"))
      (libsource (lib "") (part "R0402_1"))
    )
    (comp (ref "R76")
      (value "0")
      (footprint "R0402-Phillips")
      (description "Resistor")
      (fields (field (name "MANUFACTURER") "BOURNS") (field (name "TOLERANCE") "5%"))
      (libsource (lib "") (part "R0402_1"))
    )
    (comp (ref "R77")
      (value "0")
      (footprint "R0402-Phillips")
      (description "Resistor")
      (fields (field (name "MANUFACTURER") "BOURNS") (field (name "TOLERANCE") "5%"))
      (libsource (lib "") (part "R0402_1"))
    )
    (comp (ref "R78")
      (value "0")
      (footprint "R0402-Phillips")
      (description "Resistor")
      (fields (field (name "MANUFACTURER") "BOURNS") (field (name "TOLERANCE") "5%"))
      (libsource (lib "") (part "R0402_1"))
    )
    (comp (ref "R79")
      (value "10")
      (footprint "R0402-Phillips")
      (description "Resistor")
      (fields (field (name "MANUFACTURER") "BOURNS") (field (name "TOLERANCE") "5%"))
      (libsource (lib "") (part "R0402_1"))
    )
    (comp (ref "U1")
      (value "XC7A50T-2CPG236I")
      (footprint "CPG236")
      (description "Artix-7 FPGA")
      (fields (field (name "MANUFACTURER") "Xilinx"))
      (libsource (lib "Xilinx Artix-7") (part "XC7A35T-2CPG236C"))
    )
    (comp (ref "U2")
      (value "LMS7002M")
      (footprint "Andy:aQFN260(11.5x11.5mm)")
      (description "FPRF MIMO Transceiver IC")
      (fields (field (name "MANUFACTURER") "Lime Microsystems"))
      (libsource (lib "Andy") (part "LMS7002M"))
    )
    (comp (ref "U19")
      (value "LP8758A1E0YFFR")
      (footprint "BGA WLCSP35")
      (description "IC 4xDC/DC")
      (fields (field (name "MANUFACTURER") "TI"))
      (libsource (lib "Andy") (part "LP8758-E0"))
    )
    (comp (ref "U20")
      (value "LP8758A1E0YFFR")
      (footprint "BGA WLCSP35")
      (description "IC 4xDC/DC")
      (fields (field (name "MANUFACTURER") "TI"))
      (libsource (lib "Andy") (part "LP8758-E0"))
    )
    (comp (ref "U21")
      (value "TPS7A8801RTJT")
      (footprint "QFN-20(4X4/0.5)TI")
      (description "IC dual LDO extra low noise")
      (fields (field (name "MANUFACTURER") "TI"))
      (libsource (lib "Andy") (part "TPS7A88"))
    )
    (comp (ref "U22")
      (value "TPS7A8801RTJT")
      (footprint "QFN-20(4X4/0.5)TI")
      (description "IC dual LDO extra low noise")
      (fields (field (name "MANUFACTURER") "TI"))
      (libsource (lib "Andy") (part "TPS7A88"))
    )
    (comp (ref "U28")
      (value "MAX40200ANS+")
      (footprint "BGA WLP4 (0.7x0.7/0.35)")
      (description "IC ideal diode switch")
      (fields (field (name "MANUFACTURER") "MAXIM"))
      (libsource (lib "Andy") (part "MAX40200ANS+"))
    )
    (comp (ref "U29")
      (value "MAX40200ANS+")
      (footprint "BGA WLP4 (0.7x0.7/0.35)")
      (description "IC ideal diode switch")
      (fields (field (name "MANUFACTURER") "MAXIM"))
      (libsource (lib "Andy") (part "MAX40200ANS+"))
    )
  )
  (nets
    (net (code "1") (name "+1.0V_MGTAVCC") (class "Default")
      (node (ref "C130") (pin "2") (pinfunction "2_2") (pintype "passive"))
      (node (ref "C131") (pin "1") (pinfunction "1_1") (pintype "passive"))
      (node (ref "C132") (pin "1") (pinfunction "1_1") (pintype "passive"))
      (node (ref "L22") (pin "2") (pinfunction "2_2") (pintype "passive"))
      (node (ref "U1") (pin "C1") (pinfunction "MGTAVCC_C1") (pintype "power_in"))
      (node (ref "U1") (pin "E1") (pinfunction "MGTAVCC_E1") (pintype "power_in"))
      (node (ref "U1") (pin "F3") (pinfunction "MGTAVCC_F3") (pintype "power_in"))
      (node (ref "U1") (pin "G9") (pinfunction "MGTAVCC_G9") (pintype "power_in"))
      (node (ref "U1") (pin "H9") (pinfunction "MGTAVCC_H9") (pintype "power_in"))
    )
    (net (code "2") (name "+1.0V_VCCINT") (class "Default")
      (node (ref "C123") (pin "2") (pinfunction "2_2") (pintype "passive"))
      (node (ref "C124") (pin "2") (pinfunction "2_2") (pintype "passive"))
      (node (ref "C125") (pin "1") (pinfunction "1_1") (pintype "passive"))
      (node (ref "C126") (pin "1") (pinfunction "1_1") (pintype "passive"))
      (node (ref "C127") (pin "1") (pinfunction "1_1") (pintype "passive"))
      (node (ref "C128") (pin "1") (pinfunction "1_1") (pintype "passive"))
      (node (ref "C129") (pin "1") (pinfunction "1_1") (pintype "passive"))
      (node (ref "C164") (pin "1") (pinfunction "1_1") (pintype "passive"))
      (node (ref "C165") (pin "1") (pinfunction "1_1") (pintype "passive"))
      (node (ref "L21") (pin "2") (pinfunction "2_2") (pintype "passive"))
      (node (ref "U1") (pin "G10") (pinfunction "VCCINT_G10") (pintype "power_in"))
      (node (ref "U1") (pin "H10") (pinfunction "VCCINT_H10") (pintype "power_in"))
      (node (ref "U1") (pin "J10") (pinfunction "VCCINT_J10") (pintype "power_in"))
      (node (ref "U1") (pin "L10") (pinfunction "VCCINT_L10") (pintype "power_in"))
      (node (ref "U1") (pin "M10") (pinfunction "VCCINT_M10") (pintype "power_in"))
      (node (ref "U1") (pin "M11") (pinfunction "VCCBRAM_M11") (pintype "power_in"))
      (node (ref "U1") (pin "N10") (pinfunction "VCCINT_N10") (pintype "power_in"))
      (node (ref "U1") (pin "N11") (pinfunction "VCCBRAM_N11") (pintype "power_in"))
    )
    (net (code "3") (name "+1.2V_MGTAVTT") (class "Default")
      (node (ref "C166") (pin "1") (pinfunction "1_1") (pintype "passive"))
      (node (ref "C167") (pin "1") (pinfunction "1_1") (pintype "passive"))
      (node (ref "C168") (pin "1") (pinfunction "1_1") (pintype "passive"))
      (node (ref "L24") (pin "2") (pinfunction "2_2") (pintype "passive"))
      (node (ref "U1") (pin "B1") (pinfunction "MGTAVTT_B1") (pintype "power_in"))
      (node (ref "U1") (pin "C5") (pinfunction "MGTAVTT_C5") (pintype "power_in"))
      (node (ref "U1") (pin "E2") (pinfunction "MGTAVTT_E2") (pintype "power_in"))
      (node (ref "U1") (pin "G7") (pinfunction "MGTAVTT_G7") (pintype "power_in"))
    )
    (net (code "4") (name "+1.2V_VDLMS") (class "Default")
      (node (ref "L25") (pin "2") (pinfunction "2_2") (pintype "passive"))
      (node (ref "L28") (pin "1") (pinfunction "1_1") (pintype "passive"))
      (node (ref "L29") (pin "1") (pinfunction "1_1") (pintype "passive"))
      (node (ref "L30") (pin "1") (pinfunction "1_1") (pintype "passive"))
      (node (ref "L31") (pin "1") (pinfunction "1_1") (pintype "passive"))
      (node (ref "L45") (pin "2") (pinfunction "2_2") (pintype "passive"))
      (node (ref "R76") (pin "1") (pinfunction "1_1") (pintype "passive"))
    )
    (net (code "5") (name "+1.4V_VALMS") (class "Default")
      (node (ref "C64") (pin "2") (pinfunction "2_2") (pintype "passive"))
      (node (ref "L34") (pin "1") (pinfunction "1_1") (pintype "passive"))
      (node (ref "L46") (pin "2") (pinfunction "2_2") (pintype "passive"))
      (node (ref "L49") (pin "2") (pinfunction "2_2") (pintype "passive"))
      (node (ref "L51") (pin "2") (pinfunction "2_2") (pintype "passive"))
      (node (ref "L52") (pin "2") (pinfunction "2_2") (pintype "passive"))
      (node (ref "L53") (pin "2") (pinfunction "2_2") (pintype "passive"))
      (node (ref "L73") (pin "2") (pinfunction "2_2") (pintype "passive"))
      (node (ref "R71") (pin "2") (pinfunction "2_2") (pintype "passive"))
      (node (ref "U22") (pin "14") (pinfunction "OUT1_14") (pintype "passive"))
      (node (ref "U22") (pin "15") (pinfunction "OUT1_15") (pintype "passive"))
    )
    (net (code "6") (name "+1.5V") (class "Default")
      (node (ref "C73") (pin "2") (pinfunction "2_2") (pintype "passive"))
      (node (ref "L12") (pin "1") (pinfunction "1_1") (pintype "passive"))
      (node (ref "L20") (pin "2") (pinfunction "2_2") (pintype "passive"))
      (node (ref "U20") (pin "E2") (pinfunction "FB_B3_E2") (pintype "passive"))
    )
    (net (code "7") (name "+1.8V_VALMS") (class "Default")
      (node (ref "C62") (pin "2") (pinfunction "2_2") (pintype "passive"))
      (node (ref "L32") (pin "1") (pinfunction "1_1") (pintype "passive"))
      (node (ref "L36") (pin "1") (pinfunction "1_1") (pintype "passive"))
      (node (ref "L37") (pin "1") (pinfunction "1_1") (pintype "passive"))
      (node (ref "L40") (pin "2") (pinfunction "2_2") (pintype "passive"))
      (node (ref "L42") (pin "2") (pinfunction "2_2") (pintype "passive"))
      (node (ref "L43") (pin "2") (pinfunction "2_2") (pintype "passive"))
      (node (ref "L44") (pin "2") (pinfunction "2_2") (pintype "passive"))
      (node (ref "L47") (pin "2") (pinfunction "2_2") (pintype "passive"))
      (node (ref "R67") (pin "2") (pinfunction "2_2") (pintype "passive"))
      (node (ref "R79") (pin "2") (pinfunction "2_2") (pintype "passive"))
      (node (ref "U21") (pin "14") (pinfunction "OUT1_14") (pintype "passive"))
      (node (ref "U21") (pin "15") (pinfunction "OUT1_15") (pintype "passive"))
    )
    (net (code "8") (name "+1.8V_VCCAUX") (class "Default")
      (node (ref "C160") (pin "1") (pinfunction "1_1") (pintype "passive"))
      (node (ref "C161") (pin "1") (pinfunction "1_1") (pintype "passive"))
      (node (ref "C162") (pin "1") (pinfunction "1_1") (pintype "passive"))
      (node (ref "C163") (pin "1") (pinfunction "1_1") (pintype "passive"))
      (node (ref "L26") (pin "2") (pinfunction "2_2") (pintype "passive"))
      (node (ref "U1") (pin "C13") (pinfunction "VCCADC_0_C13") (pintype "power_in"))
      (node (ref "U1") (pin "C9") (pinfunction "VCCBATT_0_C9") (pintype "power_in"))
      (node (ref "U1") (pin "H13") (pinfunction "VCCAUX_H13") (pintype "power_in"))
      (node (ref "U1") (pin "J13") (pinfunction "VCCAUX_J13") (pintype "power_in"))
    )
    (net (code "9") (name "+1.8V_VDLMS") (class "Default")
      (node (ref "L27") (pin "2") (pinfunction "2_2") (pintype "passive"))
      (node (ref "R77") (pin "1") (pinfunction "1_1") (pintype "passive"))
    )
    (net (code "10") (name "+1.8{slash}3.3V") (class "Default")
      (node (ref "C67") (pin "2") (pinfunction "2_2") (pintype "passive"))
      (node (ref "L14") (pin "2") (pinfunction "2_2") (pintype "passive"))
      (node (ref "L23") (pin "1") (pinfunction "1_1") (pintype "passive"))
      (node (ref "U19") (pin "C2") (pinfunction "FB_B1_C2") (pintype "passive"))
    )
    (net (code "11") (name "+1.8{slash}3.3VCCIO") (class "Default")
      (node (ref "C133") (pin "2") (pinfunction "2_2") (pintype "passive"))
      (node (ref "C134") (pin "1") (pinfunction "1_1") (pintype "passive"))
      (node (ref "C135") (pin "1") (pinfunction "1_1") (pintype "passive"))
      (node (ref "C136") (pin "1") (pinfunction "1_1") (pintype "passive"))
      (node (ref "C137") (pin "1") (pinfunction "1_1") (pintype "passive"))
      (node (ref "C138") (pin "1") (pinfunction "1_1") (pintype "passive"))
      (node (ref "C139") (pin "1") (pinfunction "1_1") (pintype "passive"))
      (node (ref "C140") (pin "1") (pinfunction "1_1") (pintype "passive"))
      (node (ref "C141") (pin "1") (pinfunction "1_1") (pintype "passive"))
      (node (ref "C142") (pin "1") (pinfunction "1_1") (pintype "passive"))
      (node (ref "C143") (pin "1") (pinfunction "1_1") (pintype "passive"))
      (node (ref "C144") (pin "1") (pinfunction "1_1") (pintype "passive"))
      (node (ref "C145") (pin "1") (pinfunction "1_1") (pintype "passive"))
      (node (ref "C146") (pin "1") (pinfunction "1_1") (pintype "passive"))
      (node (ref "C147") (pin "1") (pinfunction "1_1") (pintype "passive"))
      (node (ref "C148") (pin "1") (pinfunction "1_1") (pintype "passive"))
      (node (ref "C149") (pin "1") (pinfunction "1_1") (pintype "passive"))
      (node (ref "C150") (pin "1") (pinfunction "1_1") (pintype "passive"))
      (node (ref "C151") (pin "1") (pinfunction "1_1") (pintype "passive"))
      (node (ref "C152") (pin "1") (pinfunction "1_1") (pintype "passive"))
      (node (ref "L23") (pin "2") (pinfunction "2_2") (pintype "passive"))
      (node (ref "R62") (pin "1") (pinfunction "1_1") (pintype "passive"))
      (node (ref "R64") (pin "1") (pinfunction "1_1") (pintype "passive"))
      (node (ref "R66") (pin "1") (pinfunction "1_1") (pintype "passive"))
      (node (ref "R75") (pin "1") (pinfunction "1_1") (pintype "passive"))
      (node (ref "R78") (pin "2") (pinfunction "2_2") (pintype "passive"))
      (node (ref "U1") (pin "B19") (pinfunction "VCCO_16_B19") (pintype "power_in"))
      (node (ref "U1") (pin "C14") (pinfunction "VCCO_16_C14") (pintype "power_in"))
      (node (ref "U1") (pin "C18") (pinfunction "VCCO_16_C18") (pintype "power_in"))
      (node (ref "U1") (pin "F17") (pinfunction "VCCO_14_F17") (pintype "power_in"))
      (node (ref "U1") (pin "G12") (pinfunction "VCCO_0_G12") (pintype "power_in"))
      (node (ref "U1") (pin "G13") (pinfunction "VCCO_16_G13") (pintype "power_in"))
      (node (ref "U1") (pin "K12") (pinfunction "VCCO_14_K12") (pintype "power_in"))
      (node (ref "U1") (pin "K13") (pinfunction "VCCO_14_K13") (pintype "power_in"))
      (node (ref "U1") (pin "L12") (pinfunction "VCCO_14_L12") (pintype "power_in"))
      (node (ref "U1") (pin "L13") (pinfunction "VCCO_14_L13") (pintype "power_in"))
      (node (ref "U1") (pin "M12") (pinfunction "VCCO_14_M12") (pintype "power_in"))
      (node (ref "U1") (pin "M17") (pinfunction "VCCO_14_M17") (pintype "power_in"))
      (node (ref "U1") (pin "M8") (pinfunction "VCCO_34_M8") (pintype "power_in"))
      (node (ref "U1") (pin "N7") (pinfunction "VCCO_34_N7") (pintype "power_in"))
      (node (ref "U1") (pin "N8") (pinfunction "VCCO_34_N8") (pintype "power_in"))
      (node (ref "U1") (pin "R1") (pinfunction "VCCO_34_R1") (pintype "power_in"))
      (node (ref "U1") (pin "R17") (pinfunction "VCCO_14_R17") (pintype "power_in"))
      (node (ref "U1") (pin "U13") (pinfunction "VCCO_14_U13") (pintype "power_in"))
      (node (ref "U1") (pin "V1") (pinfunction "VCCO_34_V1") (pintype "power_in"))
      (node (ref "U1") (pin "V6") (pinfunction "VCCO_34_V6") (pintype "power_in"))
      (node (ref "U1") (pin "V9") (pinfunction "VCCO_0_V9") (pintype "power_in"))
      (node (ref "U28") (pin "A1") (pinfunction "VDD_A1") (pintype "passive"))
      (node (ref "U28") (pin "B1") (pinfunction "EN_B1") (pintype "passive"))
    )
    (net (code "12") (name "+1.25V_VALMS") (class "Default")
      (node (ref "C65") (pin "2") (pinfunction "2_2") (pintype "passive"))
      (node (ref "L33") (pin "1") (pinfunction "1_1") (pintype "passive"))
      (node (ref "L38") (pin "1") (pinfunction "1_1") (pintype "passive"))
      (node (ref "L41") (pin "2") (pinfunction "2_2") (pintype "passive"))
      (node (ref "L48") (pin "2") (pinfunction "2_2") (pintype "passive"))
      (node (ref "L50") (pin "2") (pinfunction "2_2") (pintype "passive"))
      (node (ref "R73") (pin "2") (pinfunction "2_2") (pintype "passive"))
      (node (ref "U22") (pin "11") (pinfunction "OUT2_11") (pintype "passive"))
      (node (ref "U22") (pin "12") (pinfunction "OUT2_12") (pintype "passive"))
    )
    (net (code "13") (name "+1.75V") (class "Default")
      (node (ref "C72") (pin "2") (pinfunction "2_2") (pintype "passive"))
      (node (ref "L11") (pin "1") (pinfunction "1_1") (pintype "passive"))
      (node (ref "L19") (pin "2") (pinfunction "2_2") (pintype "passive"))
      (node (ref "U20") (pin "E4") (pinfunction "FB_B2_E4") (pintype "passive"))
    )
    (net (code "14") (name "+2.05V") (class "Default")
      (node (ref "C70") (pin "2") (pinfunction "2_2") (pintype "passive"))
      (node (ref "L17") (pin "2") (pinfunction "2_2") (pintype "passive"))
      (node (ref "L9") (pin "1") (pinfunction "1_1") (pintype "passive"))
      (node (ref "U20") (pin "C4") (pinfunction "FB_B0_C4") (pintype "passive"))
    )
    (net (code "15") (name "+3,3V") (class "Default")
      (node (ref "C71") (pin "2") (pinfunction "2_2") (pintype "passive"))
      (node (ref "L10") (pin "1") (pinfunction "1_1") (pintype "passive"))
      (node (ref "L18") (pin "2") (pinfunction "2_2") (pintype "passive"))
      (node (ref "L54") (pin "1") (pinfunction "1_1") (pintype "passive"))
      (node (ref "U20") (pin "C2") (pinfunction "FB_B1_C2") (pintype "passive"))
    )
    (net (code "16") (name "+3.3{slash}5VIN") (class "Default")
      (node (ref "C46") (pin "2") (pinfunction "2_2") (pintype "passive"))
      (node (ref "C47") (pin "2") (pinfunction "2_2") (pintype "passive"))
      (node (ref "C48") (pin "2") (pinfunction "2_2") (pintype "passive"))
      (node (ref "C49") (pin "2") (pinfunction "2_2") (pintype "passive"))
      (node (ref "C50") (pin "2") (pinfunction "2_2") (pintype "passive"))
      (node (ref "C51") (pin "2") (pinfunction "2_2") (pintype "passive"))
      (node (ref "C52") (pin "2") (pinfunction "2_2") (pintype "passive"))
      (node (ref "C53") (pin "2") (pinfunction "2_2") (pintype "passive"))
      (node (ref "C58") (pin "2") (pinfunction "2_2") (pintype "passive"))
      (node (ref "C59") (pin "2") (pinfunction "2_2") (pintype "passive"))
      (node (ref "R63") (pin "1") (pinfunction "1_1") (pintype "passive"))
      (node (ref "U19") (pin "A1") (pinfunction "VIN_B1_A1") (pintype "passive"))
      (node (ref "U19") (pin "A5") (pinfunction "VIN_B0_A5") (pintype "passive"))
      (node (ref "U19") (pin "B1") (pinfunction "VIN_B1_B1") (pintype "passive"))
      (node (ref "U19") (pin "B5") (pinfunction "VIN_B0_B5") (pintype "passive"))
      (node (ref "U19") (pin "E1") (pinfunction "VANA_E1") (pintype "passive"))
      (node (ref "U19") (pin "F1") (pinfunction "VIN_B3_F1") (pintype "passive"))
      (node (ref "U19") (pin "F5") (pinfunction "VIN_B2_F5") (pintype "passive"))
      (node (ref "U19") (pin "G1") (pinfunction "VIN_B3_G1") (pintype "passive"))
      (node (ref "U19") (pin "G5") (pinfunction "VIN_B2_G5") (pintype "passive"))
      (node (ref "U20") (pin "A1") (pinfunction "VIN_B1_A1") (pintype "passive"))
      (node (ref "U20") (pin "A5") (pinfunction "VIN_B0_A5") (pintype "passive"))
      (node (ref "U20") (pin "B1") (pinfunction "VIN_B1_B1") (pintype "passive"))
      (node (ref "U20") (pin "B5") (pinfunction "VIN_B0_B5") (pintype "passive"))
      (node (ref "U20") (pin "E1") (pinfunction "VANA_E1") (pintype "passive"))
      (node (ref "U20") (pin "F1") (pinfunction "VIN_B3_F1") (pintype "passive"))
      (node (ref "U20") (pin "F5") (pinfunction "VIN_B2_F5") (pintype "passive"))
      (node (ref "U20") (pin "G1") (pinfunction "VIN_B3_G1") (pintype "passive"))
      (node (ref "U20") (pin "G5") (pinfunction "VIN_B2_G5") (pintype "passive"))
    )
    (net (code "17") (name "+3V_VACLK") (class "Default")
      (node (ref "C63") (pin "2") (pinfunction "2_2") (pintype "passive"))
      (node (ref "R61") (pin "1") (pinfunction "1_1") (pintype "passive"))
      (node (ref "R65") (pin "1") (pinfunction "1_1") (pintype "passive"))
      (node (ref "R69") (pin "2") (pinfunction "2_2") (pintype "passive"))
      (node (ref "U21") (pin "11") (pinfunction "OUT2_11") (pintype "passive"))
      (node (ref "U21") (pin "12") (pinfunction "OUT2_12") (pintype "passive"))
    )
    (net (code "18") (name "/+1.0V") (class "Default")
      (node (ref "C66") (pin "1") (pinfunction "1_1") (pintype "passive"))
      (node (ref "L13") (pin "2") (pinfunction "2_2") (pintype "passive"))
      (node (ref "L21") (pin "1") (pinfunction "1_1") (pintype "passive"))
      (node (ref "L22") (pin "1") (pinfunction "1_1") (pintype "passive"))
      (node (ref "U19") (pin "C4") (pinfunction "FB_B0_C4") (pintype "passive"))
    )
    (net (code "19") (name "/+1.2V") (class "Default")
      (node (ref "C68") (pin "1") (pinfunction "1_1") (pintype "passive"))
      (node (ref "L15") (pin "2") (pinfunction "2_2") (pintype "passive"))
      (node (ref "L24") (pin "1") (pinfunction "1_1") (pintype "passive"))
      (node (ref "L25") (pin "1") (pinfunction "1_1") (pintype "passive"))
      (node (ref "U19") (pin "E4") (pinfunction "FB_B2_E4") (pintype "passive"))
    )
    (net (code "20") (name "/+1.2VDLMS") (class "Default")
      (node (ref "C77") (pin "2") (pinfunction "2_2") (pintype "passive"))
      (node (ref "C78") (pin "2") (pinfunction "2_2") (pintype "passive"))
      (node (ref "C79") (pin "2") (pinfunction "2_2") (pintype "passive"))
      (node (ref "C80") (pin "2") (pinfunction "2_2") (pintype "passive"))
      (node (ref "C81") (pin "2") (pinfunction "2_2") (pintype "passive"))
      (node (ref "R76") (pin "2") (pinfunction "2_2") (pintype "passive"))
      (node (ref "U2") (pin "AA29") (pinfunction "DIGPRVDD1_AA29") (pintype "passive"))
      (node (ref "U2") (pin "AE29") (pinfunction "DIGPRVDD1_AE29") (pintype "passive"))
      (node (ref "U2") (pin "L33") (pinfunction "DIGPRVDD1_L33") (pintype "passive"))
      (node (ref "U2") (pin "R31") (pinfunction "DIGPRVDD1_R31") (pintype "passive"))
    )
    (net (code "21") (name "/+1.8V") (class "Default")
      (node (ref "C69") (pin "2") (pinfunction "2_2") (pintype "passive"))
      (node (ref "L16") (pin "2") (pinfunction "2_2") (pintype "passive"))
      (node (ref "L26") (pin "1") (pinfunction "1_1") (pintype "passive"))
      (node (ref "L27") (pin "1") (pinfunction "1_1") (pintype "passive"))
      (node (ref "U19") (pin "E2") (pinfunction "FB_B3_E2") (pintype "passive"))
    )
    (net (code "22") (name "/+1.8{slash}3.3VDLMS") (class "Default")
      (node (ref "C117") (pin "1") (pinfunction "1_1") (pintype "passive"))
      (node (ref "C118") (pin "2") (pinfunction "2_2") (pintype "passive"))
      (node (ref "C119") (pin "2") (pinfunction "2_2") (pintype "passive"))
      (node (ref "C120") (pin "2") (pinfunction "2_2") (pintype "passive"))
      (node (ref "C121") (pin "2") (pinfunction "2_2") (pintype "passive"))
      (node (ref "R78") (pin "1") (pinfunction "1_1") (pintype "passive"))
      (node (ref "U2") (pin "AH30") (pinfunction "DIGPRVDD3_AH30") (pintype "passive"))
      (node (ref "U2") (pin "H32") (pinfunction "DIGPRVDD2_H32") (pintype "passive"))
      (node (ref "U2") (pin "T32") (pinfunction "DIGPRVDD2_T32") (pintype "passive"))
      (node (ref "U2") (pin "W31") (pinfunction "DIGPRPOC_W31") (pintype "passive"))
      (node (ref "U2") (pin "W33") (pinfunction "DIGPRVDD2_W33") (pintype "passive"))
    )
    (net (code "23") (name "/LDO1.4V") (class "Default")
      (node (ref "C76") (pin "2") (pinfunction "2_2") (pintype "passive"))
      (node (ref "L34") (pin "2") (pinfunction "2_2") (pintype "passive"))
      (node (ref "U2") (pin "K2") (pinfunction "VDDO_DIV_SXT_K2") (pintype "passive"))
      (node (ref "U2") (pin "L5") (pinfunction "VDD_DIV_SXT_L5") (pintype "passive"))
    )
    (net (code "24") (name "/LDO1.25V1") (class "Default")
      (node (ref "C75") (pin "2") (pinfunction "2_2") (pintype "passive"))
      (node (ref "L33") (pin "2") (pinfunction "2_2") (pintype "passive"))
      (node (ref "U2") (pin "J5") (pinfunction "VDD12O_VCO_SXT_J5") (pintype "passive"))
      (node (ref "U2") (pin "K6") (pinfunction "VDD12_VCO_SXT_K6") (pintype "passive"))
    )
    (net (code "25") (name "/PCI_PERST#") (class "Default")
      (node (ref "R63") (pin "2") (pinfunction "2_2") (pintype "passive"))
      (node (ref "U19") (pin "C5") (pinfunction "EN1_C5") (pintype "passive"))
      (node (ref "U19") (pin "D3") (pinfunction "EN2_D3") (pintype "passive"))
      (node (ref "U19") (pin "D4") (pinfunction "NRST_D4") (pintype "passive"))
    )
    (net (code "26") (name "/SCL1") (class "Default")
      (node (ref "R61") (pin "2") (pinfunction "2_2") (pintype "passive"))
      (node (ref "U19") (pin "E5") (pinfunction "SCL_E5") (pintype "passive"))
    )
    (net (code "27") (name "/SCL2") (class "Default")
      (node (ref "R62") (pin "2") (pinfunction "2_2") (pintype "passive"))
      (node (ref "U20") (pin "E5") (pinfunction "SCL_E5") (pintype "passive"))
    )
    (net (code "28") (name "/SDA1") (class "Default")
      (node (ref "R65") (pin "2") (pinfunction "2_2") (pintype "passive"))
      (node (ref "U19") (pin "D5") (pinfunction "SDA_D5") (pintype "passive"))
    )
    (net (code "29") (name "/SDA2") (class "Default")
      (node (ref "R66") (pin "2") (pinfunction "2_2") (pintype "passive"))
      (node (ref "U20") (pin "D5") (pinfunction "SDA_D5") (pintype "passive"))
    )
    (net (code "30") (name "/VCC_SEL") (class "Default")
      (node (ref "U29") (pin "B1") (pinfunction "EN_B1") (pintype "passive"))
    )
    (net (code "31") (name "GND") (class "Default")
      (node (ref "C100") (pin "2") (pinfunction "2_2") (pintype "passive"))
      (node (ref "C101") (pin "2") (pinfunction "2_2") (pintype "passive"))
      (node (ref "C102") (pin "2") (pinfunction "2_2") (pintype "passive"))
      (node (ref "C103") (pin "2") (pinfunction "2_2") (pintype "passive"))
      (node (ref "C104") (pin "2") (pinfunction "2_2") (pintype "passive"))
      (node (ref "C105") (pin "2") (pinfunction "2_2") (pintype "passive"))
      (node (ref "C106") (pin "2") (pinfunction "2_2") (pintype "passive"))
      (node (ref "C107") (pin "2") (pinfunction "2_2") (pintype "passive"))
      (node (ref "C108") (pin "2") (pinfunction "2_2") (pintype "passive"))
      (node (ref "C109") (pin "2") (pinfunction "2_2") (pintype "passive"))
      (node (ref "C110") (pin "2") (pinfunction "2_2") (pintype "passive"))
      (node (ref "C111") (pin "2") (pinfunction "2_2") (pintype "passive"))
      (node (ref "C112") (pin "2") (pinfunction "2_2") (pintype "passive"))
      (node (ref "C113") (pin "2") (pinfunction "2_2") (pintype "passive"))
      (node (ref "C114") (pin "2") (pinfunction "2_2") (pintype "passive"))
      (node (ref "C115") (pin "2") (pinfunction "2_2") (pintype "passive"))
      (node (ref "C116") (pin "2") (pinfunction "2_2") (pintype "passive"))
      (node (ref "C117") (pin "2") (pinfunction "2_2") (pintype "passive"))
      (node (ref "C118") (pin "1") (pinfunction "1_1") (pintype "passive"))
      (node (ref "C119") (pin "1") (pinfunction "1_1") (pintype "passive"))
      (node (ref "C120") (pin "1") (pinfunction "1_1") (pintype "passive"))
      (node (ref "C121") (pin "1") (pinfunction "1_1") (pintype "passive"))
      (node (ref "C122") (pin "2") (pinfunction "2_2") (pintype "passive"))
      (node (ref "C123") (pin "1") (pinfunction "1_1") (pintype "passive"))
      (node (ref "C124") (pin "1") (pinfunction "1_1") (pintype "passive"))
      (node (ref "C125") (pin "2") (pinfunction "2_2") (pintype "passive"))
      (node (ref "C126") (pin "2") (pinfunction "2_2") (pintype "passive"))
      (node (ref "C127") (pin "2") (pinfunction "2_2") (pintype "passive"))
      (node (ref "C128") (pin "2") (pinfunction "2_2") (pintype "passive"))
      (node (ref "C129") (pin "2") (pinfunction "2_2") (pintype "passive"))
      (node (ref "C130") (pin "1") (pinfunction "1_1") (pintype "passive"))
      (node (ref "C131") (pin "2") (pinfunction "2_2") (pintype "passive"))
      (node (ref "C132") (pin "2") (pinfunction "2_2") (pintype "passive"))
      (node (ref "C133") (pin "1") (pinfunction "1_1") (pintype "passive"))
      (node (ref "C134") (pin "2") (pinfunction "2_2") (pintype "passive"))
      (node (ref "C135") (pin "2") (pinfunction "2_2") (pintype "passive"))
      (node (ref "C136") (pin "2") (pinfunction "2_2") (pintype "passive"))
      (node (ref "C137") (pin "2") (pinfunction "2_2") (pintype "passive"))
      (node (ref "C138") (pin "2") (pinfunction "2_2") (pintype "passive"))
      (node (ref "C139") (pin "2") (pinfunction "2_2") (pintype "passive"))
      (node (ref "C140") (pin "2") (pinfunction "2_2") (pintype "passive"))
      (node (ref "C141") (pin "2") (pinfunction "2_2") (pintype "passive"))
      (node (ref "C142") (pin "2") (pinfunction "2_2") (pintype "passive"))
      (node (ref "C143") (pin "2") (pinfunction "2_2") (pintype "passive"))
      (node (ref "C144") (pin "2") (pinfunction "2_2") (pintype "passive"))
      (node (ref "C145") (pin "2") (pinfunction "2_2") (pintype "passive"))
      (node (ref "C146") (pin "2") (pinfunction "2_2") (pintype "passive"))
      (node (ref "C147") (pin "2") (pinfunction "2_2") (pintype "passive"))
      (node (ref "C148") (pin "2") (pinfunction "2_2") (pintype "passive"))
      (node (ref "C149") (pin "2") (pinfunction "2_2") (pintype "passive"))
      (node (ref "C150") (pin "2") (pinfunction "2_2") (pintype "passive"))
      (node (ref "C151") (pin "2") (pinfunction "2_2") (pintype "passive"))
      (node (ref "C152") (pin "2") (pinfunction "2_2") (pintype "passive"))
      (node (ref "C153") (pin "2") (pinfunction "2_2") (pintype "passive"))
      (node (ref "C154") (pin "2") (pinfunction "2_2") (pintype "passive"))
      (node (ref "C155") (pin "2") (pinfunction "2_2") (pintype "passive"))
      (node (ref "C156") (pin "2") (pinfunction "2_2") (pintype "passive"))
      (node (ref "C157") (pin "2") (pinfunction "2_2") (pintype "passive"))
      (node (ref "C158") (pin "2") (pinfunction "2_2") (pintype "passive"))
      (node (ref "C159") (pin "2") (pinfunction "2_2") (pintype "passive"))
      (node (ref "C160") (pin "2") (pinfunction "2_2") (pintype "passive"))
      (node (ref "C161") (pin "2") (pinfunction "2_2") (pintype "passive"))
      (node (ref "C162") (pin "2") (pinfunction "2_2") (pintype "passive"))
      (node (ref "C163") (pin "2") (pinfunction "2_2") (pintype "passive"))
      (node (ref "C164") (pin "2") (pinfunction "2_2") (pintype "passive"))
      (node (ref "C165") (pin "2") (pinfunction "2_2") (pintype "passive"))
      (node (ref "C166") (pin "2") (pinfunction "2_2") (pintype "passive"))
      (node (ref "C167") (pin "2") (pinfunction "2_2") (pintype "passive"))
      (node (ref "C168") (pin "2") (pinfunction "2_2") (pintype "passive"))
      (node (ref "C44") (pin "1") (pinfunction "1_1") (pintype "passive"))
      (node (ref "C45") (pin "1") (pinfunction "1_1") (pintype "passive"))
      (node (ref "C46") (pin "1") (pinfunction "1_1") (pintype "passive"))
      (node (ref "C47") (pin "1") (pinfunction "1_1") (pintype "passive"))
      (node (ref "C48") (pin "1") (pinfunction "1_1") (pintype "passive"))
      (node (ref "C49") (pin "1") (pinfunction "1_1") (pintype "passive"))
      (node (ref "C50") (pin "1") (pinfunction "1_1") (pintype "passive"))
      (node (ref "C51") (pin "1") (pinfunction "1_1") (pintype "passive"))
      (node (ref "C52") (pin "1") (pinfunction "1_1") (pintype "passive"))
      (node (ref "C53") (pin "1") (pinfunction "1_1") (pintype "passive"))
      (node (ref "C54") (pin "1") (pinfunction "1_1") (pintype "passive"))
      (node (ref "C55") (pin "1") (pinfunction "1_1") (pintype "passive"))
      (node (ref "C56") (pin "1") (pinfunction "1_1") (pintype "passive"))
      (node (ref "C57") (pin "1") (pinfunction "1_1") (pintype "passive"))
      (node (ref "C58") (pin "1") (pinfunction "1_1") (pintype "passive"))
      (node (ref "C59") (pin "1") (pinfunction "1_1") (pintype "passive"))
      (node (ref "C60") (pin "1") (pinfunction "1_1") (pintype "passive"))
      (node (ref "C61") (pin "1") (pinfunction "1_1") (pintype "passive"))
      (node (ref "C62") (pin "1") (pinfunction "1_1") (pintype "passive"))
      (node (ref "C63") (pin "1") (pinfunction "1_1") (pintype "passive"))
      (node (ref "C64") (pin "1") (pinfunction "1_1") (pintype "passive"))
      (node (ref "C65") (pin "1") (pinfunction "1_1") (pintype "passive"))
      (node (ref "C66") (pin "2") (pinfunction "2_2") (pintype "passive"))
      (node (ref "C67") (pin "1") (pinfunction "1_1") (pintype "passive"))
      (node (ref "C68") (pin "2") (pinfunction "2_2") (pintype "passive"))
      (node (ref "C69") (pin "1") (pinfunction "1_1") (pintype "passive"))
      (node (ref "C70") (pin "1") (pinfunction "1_1") (pintype "passive"))
      (node (ref "C71") (pin "1") (pinfunction "1_1") (pintype "passive"))
      (node (ref "C72") (pin "1") (pinfunction "1_1") (pintype "passive"))
      (node (ref "C73") (pin "1") (pinfunction "1_1") (pintype "passive"))
      (node (ref "C74") (pin "1") (pinfunction "1_1") (pintype "passive"))
      (node (ref "C75") (pin "1") (pinfunction "1_1") (pintype "passive"))
      (node (ref "C76") (pin "1") (pinfunction "1_1") (pintype "passive"))
      (node (ref "C77") (pin "1") (pinfunction "1_1") (pintype "passive"))
      (node (ref "C78") (pin "1") (pinfunction "1_1") (pintype "passive"))
      (node (ref "C79") (pin "1") (pinfunction "1_1") (pintype "passive"))
      (node (ref "C80") (pin "1") (pinfunction "1_1") (pintype "passive"))
      (node (ref "C81") (pin "1") (pinfunction "1_1") (pintype "passive"))
      (node (ref "C82") (pin "1") (pinfunction "1_1") (pintype "passive"))
      (node (ref "C83") (pin "1") (pinfunction "1_1") (pintype "passive"))
      (node (ref "C84") (pin "1") (pinfunction "1_1") (pintype "passive"))
      (node (ref "C85") (pin "1") (pinfunction "1_1") (pintype "passive"))
      (node (ref "C86") (pin "1") (pinfunction "1_1") (pintype "passive"))
      (node (ref "C87") (pin "1") (pinfunction "1_1") (pintype "passive"))
      (node (ref "C88") (pin "1") (pinfunction "1_1") (pintype "passive"))
      (node (ref "C89") (pin "1") (pinfunction "1_1") (pintype "passive"))
      (node (ref "C90") (pin "1") (pinfunction "1_1") (pintype "passive"))
      (node (ref "C91") (pin "1") (pinfunction "1_1") (pintype "passive"))
      (node (ref "C92") (pin "1") (pinfunction "1_1") (pintype "passive"))
      (node (ref "C93") (pin "1") (pinfunction "1_1") (pintype "passive"))
      (node (ref "C94") (pin "1") (pinfunction "1_1") (pintype "passive"))
      (node (ref "C95") (pin "1") (pinfunction "1_1") (pintype "passive"))
      (node (ref "C96") (pin "2") (pinfunction "2_2") (pintype "passive"))
      (node (ref "C97") (pin "2") (pinfunction "2_2") (pintype "passive"))
      (node (ref "C98") (pin "2") (pinfunction "2_2") (pintype "passive"))
      (node (ref "C99") (pin "2") (pinfunction "2_2") (pintype "passive"))
      (node (ref "R68") (pin "2") (pinfunction "2_2") (pintype "passive"))
      (node (ref "R70") (pin "2") (pinfunction "2_2") (pintype "passive"))
      (node (ref "R72") (pin "2") (pinfunction "2_2") (pintype "passive"))
      (node (ref "R74") (pin "2") (pinfunction "2_2") (pintype "passive"))
      (node (ref "U1") (pin "A1") (pinfunction "GND_A1") (pintype "power_in"))
      (node (ref "U1") (pin "A19") (pinfunction "GND_A19") (pintype "power_in"))
      (node (ref "U1") (pin "A3") (pinfunction "GND_A3") (pintype "power_in"))
      (node (ref "U1") (pin "A5") (pinfunction "GND_A5") (pintype "power_in"))
      (node (ref "U1") (pin "A7") (pinfunction "GND_A7") (pintype "power_in"))
      (node (ref "U1") (pin "A9") (pinfunction "GND_A9") (pintype "power_in"))
      (node (ref "U1") (pin "B14") (pinfunction "GND_B14") (pintype "power_in"))
      (node (ref "U1") (pin "B3") (pinfunction "GND_B3") (pintype "power_in"))
      (node (ref "U1") (pin "B5") (pinfunction "GND_B5") (pintype "power_in"))
      (node (ref "U1") (pin "B7") (pinfunction "GND_B7") (pintype "power_in"))
      (node (ref "U1") (pin "B9") (pinfunction "GND_B9") (pintype "power_in"))
      (node (ref "U1") (pin "C10") (pinfunction "GND_C10") (pintype "power_in"))
      (node (ref "U1") (pin "C12") (pinfunction "GNDADC_0_C12") (pintype "power_in"))
      (node (ref "U1") (pin "C19") (pinfunction "GND_C19") (pintype "power_in"))
      (node (ref "U1") (pin "C2") (pinfunction "GND_C2") (pintype "power_in"))
      (node (ref "U1") (pin "C3") (pinfunction "GND_C3") (pintype "power_in"))
      (node (ref "U1") (pin "C4") (pinfunction "GND_C4") (pintype "power_in"))
      (node (ref "U1") (pin "C6") (pinfunction "GND_C6") (pintype "power_in"))
      (node (ref "U1") (pin "D3") (pinfunction "GND_D3") (pintype "power_in"))
      (node (ref "U1") (pin "E17") (pinfunction "GND_E17") (pintype "power_in"))
      (node (ref "U1") (pin "E3") (pinfunction "GND_E3") (pintype "power_in"))
      (node (ref "U1") (pin "F1") (pinfunction "GND_F1") (pintype "power_in"))
      (node (ref "U1") (pin "F19") (pinfunction "GND_F19") (pintype "power_in"))
      (node (ref "U1") (pin "F2") (pinfunction "GND_F2") (pintype "power_in"))
      (node (ref "U1") (pin "G1") (pinfunction "GND_G1") (pintype "power_in"))
      (node (ref "U1") (pin "G11") (pinfunction "GND_G11") (pintype "power_in"))
      (node (ref "U1") (pin "G8") (pinfunction "GND_G8") (pintype "power_in"))
      (node (ref "U1") (pin "H11") (pinfunction "GND_H11") (pintype "power_in"))
      (node (ref "U1") (pin "H12") (pinfunction "GND_H12") (pintype "power_in"))
      (node (ref "U1") (pin "H18") (pinfunction "GND_H18") (pintype "power_in"))
      (node (ref "U1") (pin "H7") (pinfunction "GND_H7") (pintype "power_in"))
      (node (ref "U1") (pin "H8") (pinfunction "GND_H8") (pintype "power_in"))
      (node (ref "U1") (pin "J11") (pinfunction "GND_J11") (pintype "power_in"))
      (node (ref "U1") (pin "J12") (pinfunction "GND_J12") (pintype "power_in"))
      (node (ref "U1") (pin "J8") (pinfunction "GND_J8") (pintype "power_in"))
      (node (ref "U1") (pin "J9") (pinfunction "GND_J9") (pintype "power_in"))
      (node (ref "U1") (pin "K8") (pinfunction "GND_K8") (pintype "power_in"))
      (node (ref "U1") (pin "L11") (pinfunction "GND_L11") (pintype "power_in"))
      (node (ref "U1") (pin "L19") (pinfunction "GND_L19") (pintype "power_in"))
      (node (ref "U1") (pin "L8") (pinfunction "GND_L8") (pintype "power_in"))
      (node (ref "U1") (pin "L9") (pinfunction "GND_L9") (pintype "power_in"))
      (node (ref "U1") (pin "M13") (pinfunction "GND_M13") (pintype "power_in"))
      (node (ref "U1") (pin "M9") (pinfunction "GND_M9") (pintype "power_in"))
      (node (ref "U1") (pin "N12") (pinfunction "GND_N12") (pintype "power_in"))
      (node (ref "U1") (pin "N13") (pinfunction "GND_N13") (pintype "power_in"))
      (node (ref "U1") (pin "N9") (pinfunction "GND_N9") (pintype "power_in"))
      (node (ref "U1") (pin "P2") (pinfunction "GND_P2") (pintype "power_in"))
      (node (ref "U1") (pin "T19") (pinfunction "GND_T19") (pintype "power_in"))
      (node (ref "U1") (pin "U6") (pinfunction "GND_U6") (pintype "power_in"))
      (node (ref "U1") (pin "U9") (pinfunction "GND_U9") (pintype "power_in"))
      (node (ref "U1") (pin "V18") (pinfunction "GND_V18") (pintype "power_in"))
      (node (ref "U1") (pin "W1") (pinfunction "GND_W1") (pintype "power_in"))
      (node (ref "U1") (pin "W12") (pinfunction "GND_W12") (pintype "power_in"))
      (node (ref "U19") (pin "A3") (pinfunction "PGND_B01_A3") (pintype "passive"))
      (node (ref "U19") (pin "B3") (pinfunction "PGND_B01_B3") (pintype "passive"))
      (node (ref "U19") (pin "C1") (pinfunction "SGND_C1") (pintype "passive"))
      (node (ref "U19") (pin "C3") (pinfunction "PGND_B01_C3") (pintype "passive"))
      (node (ref "U19") (pin "D1") (pinfunction "AGND_D1") (pintype "passive"))
      (node (ref "U19") (pin "E3") (pinfunction "PGND_B23_E3") (pintype "passive"))
      (node (ref "U19") (pin "F3") (pinfunction "PGND_B23_F3") (pintype "passive"))
      (node (ref "U19") (pin "G3") (pinfunction "PGND_B23_G3") (pintype "passive"))
      (node (ref "U2") (pin "0") (pinfunction "GND_0") (pintype "passive"))
      (node (ref "U2") (pin "AA31") (pinfunction "DIGPRGND1_AA31") (pintype "passive"))
      (node (ref "U2") (pin "AF32") (pinfunction "DIGPRGND2_AF32") (pintype "passive"))
      (node (ref "U2") (pin "AG29") (pinfunction "DIGPRGND1_AG29") (pintype "passive"))
      (node (ref "U2") (pin "AJ19") (pinfunction "GND_CP_SXR_AJ19") (pintype "passive"))
      (node (ref "U2") (pin "AK20") (pinfunction "GND_DIV_SXR_AK20") (pintype "passive"))
      (node (ref "U2") (pin "AL23") (pinfunction "GND_VCO_SXR_AL23") (pintype "passive"))
      (node (ref "U2") (pin "AM22") (pinfunction "DGND_SXR_AM22") (pintype "passive"))
      (node (ref "U2") (pin "AN25") (pinfunction "GND_RXBUF_AN25") (pintype "passive"))
      (node (ref "U2") (pin "B18") (pinfunction "DGND_CGEN_B18") (pintype "passive"))
      (node (ref "U2") (pin "B20") (pinfunction "GND_CP_CGEN_B20") (pintype "passive"))
      (node (ref "U2") (pin "C23") (pinfunction "GND_DIG_C23") (pintype "passive"))
      (node (ref "U2") (pin "C7") (pinfunction "GND_TLOBUF_TRF_C7") (pintype "passive"))
      (node (ref "U2") (pin "D20") (pinfunction "GND_DIV_CGEN_D20") (pintype "passive"))
      (node (ref "U2") (pin "E25") (pinfunction "GND_SPI_BUF_E25") (pintype "passive"))
      (node (ref "U2") (pin "F6") (pinfunction "GND_TXBUF_F6") (pintype "passive"))
      (node (ref "U2") (pin "G31") (pinfunction "DIGPRGND2_G31") (pintype "passive"))
      (node (ref "U2") (pin "H2") (pinfunction "GND_VCO_SXT_H2") (pintype "passive"))
      (node (ref "U2") (pin "J33") (pinfunction "DIGPRGND1_J33") (pintype "passive"))
      (node (ref "U2") (pin "K4") (pinfunction "GND_CP_SXT_K4") (pintype "passive"))
      (node (ref "U2") (pin "L3") (pinfunction "GND_DIV_SXT_L3") (pintype "passive"))
      (node (ref "U2") (pin "N3") (pinfunction "DGND_SXT_N3") (pintype "passive"))
      (node (ref "U2") (pin "T30") (pinfunction "DIGPRGND1_T30") (pintype "passive"))
      (node (ref "U2") (pin "W29") (pinfunction "DIGPRGND1_W29") (pintype "passive"))
      (node (ref "U2") (pin "Y30") (pinfunction "DIGPRGND2_Y30") (pintype "passive"))
      (node (ref "U20") (pin "A3") (pinfunction "PGND_B01_A3") (pintype "passive"))
      (node (ref "U20") (pin "B3") (pinfunction "PGND_B01_B3") (pintype "passive"))
      (node (ref "U20") (pin "C1") (pinfunction "SGND_C1") (pintype "passive"))
      (node (ref "U20") (pin "C3") (pinfunction "PGND_B01_C3") (pintype "passive"))
      (node (ref "U20") (pin "C5") (pinfunction "EN1_C5") (pintype "passive"))
      (node (ref "U20") (pin "D1") (pinfunction "AGND_D1") (pintype "passive"))
      (node (ref "U20") (pin "D3") (pinfunction "EN2_D3") (pintype "passive"))
      (node (ref "U20") (pin "E3") (pinfunction "PGND_B23_E3") (pintype "passive"))
      (node (ref "U20") (pin "F3") (pinfunction "PGND_B23_F3") (pintype "passive"))
      (node (ref "U20") (pin "G3") (pinfunction "PGND_B23_G3") (pintype "passive"))
      (node (ref "U21") (pin "0") (pinfunction "GND_0") (pintype "passive"))
      (node (ref "U21") (pin "13") (pinfunction "GND_13") (pintype "passive"))
      (node (ref "U21") (pin "18") (pinfunction "SS1_18") (pintype "passive"))
      (node (ref "U21") (pin "3") (pinfunction "GND_3") (pintype "passive"))
      (node (ref "U21") (pin "8") (pinfunction "SS2_8") (pintype "passive"))
      (node (ref "U22") (pin "0") (pinfunction "GND_0") (pintype "passive"))
      (node (ref "U22") (pin "13") (pinfunction "GND_13") (pintype "passive"))
      (node (ref "U22") (pin "18") (pinfunction "SS1_18") (pintype "passive"))
      (node (ref "U22") (pin "3") (pinfunction "GND_3") (pintype "passive"))
      (node (ref "U22") (pin "8") (pinfunction "SS2_8") (pintype "passive"))
      (node (ref "U28") (pin "B2") (pinfunction "G_B2") (pintype "passive"))
      (node (ref "U29") (pin "B2") (pinfunction "G_B2") (pintype "passive"))
    )
    (net (code "32") (name "Net-(C74-Pad2)") (class "Default")
      (node (ref "C74") (pin "2") (pinfunction "2_2") (pintype "passive"))
      (node (ref "L35") (pin "1") (pinfunction "1_1") (pintype "passive"))
      (node (ref "R75") (pin "2") (pinfunction "2_2") (pintype "passive"))
    )
    (net (code "33") (name "Net-(C122-Pad1)") (class "Default")
      (node (ref "C122") (pin "1") (pinfunction "1_1") (pintype "passive"))
      (node (ref "L39") (pin "2") (pinfunction "2_2") (pintype "passive"))
      (node (ref "R79") (pin "1") (pinfunction "1_1") (pintype "passive"))
    )
    (net (code "34") (name "Net-(L13-Pad1)") (class "Default")
      (node (ref "L13") (pin "1") (pinfunction "1_1") (pintype "passive"))
      (node (ref "U19") (pin "A4") (pinfunction "SW_B0_A4") (pintype "passive"))
      (node (ref "U19") (pin "B4") (pinfunction "SW_B0_B4") (pintype "passive"))
    )
    (net (code "35") (name "Net-(L14-Pad1)") (class "Default")
      (node (ref "L14") (pin "1") (pinfunction "1_1") (pintype "passive"))
      (node (ref "U19") (pin "A2") (pinfunction "SW_B1_A2") (pintype "passive"))
      (node (ref "U19") (pin "B2") (pinfunction "SW_B1_B2") (pintype "passive"))
    )
    (net (code "36") (name "Net-(L15-Pad1)") (class "Default")
      (node (ref "L15") (pin "1") (pinfunction "1_1") (pintype "passive"))
      (node (ref "U19") (pin "F4") (pinfunction "SW_B2_F4") (pintype "passive"))
      (node (ref "U19") (pin "G4") (pinfunction "SW_B2_G4") (pintype "passive"))
    )
    (net (code "37") (name "Net-(L16-Pad1)") (class "Default")
      (node (ref "L16") (pin "1") (pinfunction "1_1") (pintype "passive"))
      (node (ref "U19") (pin "F2") (pinfunction "SW_B3_F2") (pintype "passive"))
      (node (ref "U19") (pin "G2") (pinfunction "SW_B3_G2") (pintype "passive"))
    )
    (net (code "38") (name "Net-(L17-Pad1)") (class "Default")
      (node (ref "L17") (pin "1") (pinfunction "1_1") (pintype "passive"))
      (node (ref "U20") (pin "A4") (pinfunction "SW_B0_A4") (pintype "passive"))
      (node (ref "U20") (pin "B4") (pinfunction "SW_B0_B4") (pintype "passive"))
    )
    (net (code "39") (name "Net-(L18-Pad1)") (class "Default")
      (node (ref "L18") (pin "1") (pinfunction "1_1") (pintype "passive"))
      (node (ref "U20") (pin "A2") (pinfunction "SW_B1_A2") (pintype "passive"))
      (node (ref "U20") (pin "B2") (pinfunction "SW_B1_B2") (pintype "passive"))
    )
    (net (code "40") (name "Net-(L19-Pad1)") (class "Default")
      (node (ref "L19") (pin "1") (pinfunction "1_1") (pintype "passive"))
      (node (ref "U20") (pin "F4") (pinfunction "SW_B2_F4") (pintype "passive"))
      (node (ref "U20") (pin "G4") (pinfunction "SW_B2_G4") (pintype "passive"))
    )
    (net (code "41") (name "Net-(L20-Pad1)") (class "Default")
      (node (ref "L20") (pin "1") (pinfunction "1_1") (pintype "passive"))
      (node (ref "U20") (pin "F2") (pinfunction "SW_B3_F2") (pintype "passive"))
      (node (ref "U20") (pin "G2") (pinfunction "SW_B3_G2") (pintype "passive"))
    )
    (net (code "42") (name "Net-(U2B-DVDD_CGEN)") (class "Default")
      (node (ref "C100") (pin "1") (pinfunction "1_1") (pintype "passive"))
      (node (ref "L45") (pin "1") (pinfunction "1_1") (pintype "passive"))
      (node (ref "U2") (pin "A17") (pinfunction "DVDD_CGEN_A17") (pintype "passive"))
    )
    (net (code "43") (name "Net-(U2B-DVDD_SXR)") (class "Default")
      (node (ref "C92") (pin "2") (pinfunction "2_2") (pintype "passive"))
      (node (ref "L30") (pin "2") (pinfunction "2_2") (pintype "passive"))
      (node (ref "U2") (pin "AL21") (pinfunction "DVDD_SXR_AL21") (pintype "passive"))
    )
    (net (code "44") (name "Net-(U2B-DVDD_SXT)") (class "Default")
      (node (ref "C93") (pin "2") (pinfunction "2_2") (pintype "passive"))
      (node (ref "L31") (pin "2") (pinfunction "2_2") (pintype "passive"))
      (node (ref "U2") (pin "M4") (pinfunction "DVDD_SXT_M4") (pintype "passive"))
    )
    (net (code "45") (name "Net-(U2B-VDD12_DIG)") (class "Default")
      (node (ref "C90") (pin "2") (pinfunction "2_2") (pintype "passive"))
      (node (ref "L28") (pin "2") (pinfunction "2_2") (pintype "passive"))
      (node (ref "U2") (pin "C25") (pinfunction "VDD12_DIG_C25") (pintype "passive"))
    )
    (net (code "46") (name "Net-(U2B-VDD12_LNA_RFE)") (class "Default")
      (node (ref "C87") (pin "2") (pinfunction "2_2") (pintype "passive"))
      (node (ref "U2") (pin "AG5") (pinfunction "VDD12_LNA_RFE_AG5") (pintype "passive"))
    )
    (net (code "47") (name "Net-(U2B-VDD12_RXBUF)") (class "Default")
      (node (ref "C110") (pin "1") (pinfunction "1_1") (pintype "passive"))
      (node (ref "U2") (pin "AP26") (pinfunction "VDD12_RXBUF_AP26") (pintype "passive"))
    )
    (net (code "48") (name "Net-(U2B-VDD12_TIA_RFE)") (class "Default")
      (node (ref "C86") (pin "2") (pinfunction "2_2") (pintype "passive"))
      (node (ref "U2") (pin "AD6") (pinfunction "VDD12_TIA_RFE_AD6") (pintype "passive"))
    )
    (net (code "49") (name "Net-(U2B-VDD12_TXBUF)") (class "Default")
      (node (ref "C83") (pin "2") (pinfunction "2_2") (pintype "passive"))
      (node (ref "U2") (pin "G5") (pinfunction "VDD12_TXBUF_G5") (pintype "passive"))
    )
    (net (code "50") (name "Net-(U2B-VDD12_VCO_SXR)") (class "Default")
      (node (ref "C105") (pin "1") (pinfunction "1_1") (pintype "passive"))
      (node (ref "L48") (pin "1") (pinfunction "1_1") (pintype "passive"))
      (node (ref "U2") (pin "AN23") (pinfunction "VDD12_VCO_SXR_AN23") (pintype "passive"))
    )
    (net (code "51") (name "Net-(U2B-VDD14_LNA_RFE)") (class "Default")
      (node (ref "C113") (pin "1") (pinfunction "1_1") (pintype "passive"))
      (node (ref "L51") (pin "1") (pinfunction "1_1") (pintype "passive"))
      (node (ref "U2") (pin "AF6") (pinfunction "VDD14_LNA_RFE_AF6") (pintype "passive"))
    )
    (net (code "52") (name "Net-(U2B-VDD14_RBB)") (class "Default")
      (node (ref "C114") (pin "1") (pinfunction "1_1") (pintype "passive"))
      (node (ref "L52") (pin "1") (pinfunction "1_1") (pintype "passive"))
      (node (ref "U2") (pin "AD4") (pinfunction "VDD14_RBB_AD4") (pintype "passive"))
    )
    (net (code "53") (name "Net-(U2B-VDD14_TIA_RFE)") (class "Default")
      (node (ref "C115") (pin "1") (pinfunction "1_1") (pintype "passive"))
      (node (ref "L53") (pin "1") (pinfunction "1_1") (pintype "passive"))
      (node (ref "U2") (pin "AF2") (pinfunction "VDD14_TIA_RFE_AF2") (pintype "passive"))
    )
    (net (code "54") (name "Net-(U2B-VDD14_VCO_CGEN)") (class "Default")
      (node (ref "C103") (pin "1") (pinfunction "1_1") (pintype "passive"))
      (node (ref "L46") (pin "1") (pinfunction "1_1") (pintype "passive"))
      (node (ref "U2") (pin "C21") (pinfunction "VDD14_VCO_CGEN_C21") (pintype "passive"))
    )
    (net (code "55") (name "Net-(U2B-VDD18_BIAS)") (class "Default")
      (node (ref "C96") (pin "1") (pinfunction "1_1") (pintype "passive"))
      (node (ref "L42") (pin "1") (pinfunction "1_1") (pintype "passive"))
      (node (ref "U2") (pin "E17") (pinfunction "VDD18_BIAS_E17") (pintype "passive"))
    )
    (net (code "56") (name "Net-(U2B-VDD18_DIG)") (class "Default")
      (node (ref "C89") (pin "2") (pinfunction "2_2") (pintype "passive"))
      (node (ref "R77") (pin "2") (pinfunction "2_2") (pintype "passive"))
      (node (ref "U2") (pin "D24") (pinfunction "VDD18_DIG_D24") (pintype "passive"))
    )
    (net (code "57") (name "Net-(U2B-VDD18_LDO_RX)") (class "Default")
      (node (ref "C85") (pin "2") (pinfunction "2_2") (pintype "passive"))
      (node (ref "L37") (pin "2") (pinfunction "2_2") (pintype "passive"))
      (node (ref "U2") (pin "AE3") (pinfunction "VDD18_TIA_RFE_AE3") (pintype "passive"))
      (node (ref "U2") (pin "AF4") (pinfunction "VDD18_LDO_RX_AF4") (pintype "passive"))
    )
    (net (code "58") (name "Net-(U2B-VDD18_LDO_TX)") (class "Default")
      (node (ref "C84") (pin "2") (pinfunction "2_2") (pintype "passive"))
      (node (ref "L36") (pin "2") (pinfunction "2_2") (pintype "passive"))
      (node (ref "U2") (pin "N1") (pinfunction "VDD18_LDO_TX_N1") (pintype "passive"))
    )
    (net (code "59") (name "Net-(U2B-VDD18_RXBUF)") (class "Default")
      (node (ref "C111") (pin "1") (pinfunction "1_1") (pintype "passive"))
      (node (ref "L39") (pin "1") (pinfunction "1_1") (pintype "passive"))
      (node (ref "U2") (pin "AM26") (pinfunction "VDD18_RXBUF_AM26") (pintype "passive"))
    )
    (net (code "60") (name "Net-(U2B-VDD18_SXR)") (class "Default")
      (node (ref "C104") (pin "1") (pinfunction "1_1") (pintype "passive"))
      (node (ref "L47") (pin "1") (pinfunction "1_1") (pintype "passive"))
      (node (ref "U2") (pin "AM18") (pinfunction "VDD18_SXR_AM18") (pintype "passive"))
    )
    (net (code "61") (name "Net-(U2B-VDD18_TRF)") (class "Default")
      (node (ref "C97") (pin "1") (pinfunction "1_1") (pintype "passive"))
      (node (ref "L43") (pin "1") (pinfunction "1_1") (pintype "passive"))
      (node (ref "U2") (pin "D16") (pinfunction "VDD18_TRF_D16") (pintype "passive"))
    )
    (net (code "62") (name "Net-(U2B-VDD18_TXBUF)") (class "Default")
      (node (ref "C94") (pin "2") (pinfunction "2_2") (pintype "passive"))
      (node (ref "L35") (pin "2") (pinfunction "2_2") (pintype "passive"))
      (node (ref "U2") (pin "H6") (pinfunction "VDD18_TXBUF_H6") (pintype "passive"))
    )
    (net (code "63") (name "Net-(U2B-VDD18_VCO_CGEN)") (class "Default")
      (node (ref "C98") (pin "1") (pinfunction "1_1") (pintype "passive"))
      (node (ref "L44") (pin "1") (pinfunction "1_1") (pintype "passive"))
      (node (ref "U2") (pin "E21") (pinfunction "VDD18_VCO_CGEN_E21") (pintype "passive"))
    )
    (net (code "64") (name "Net-(U2B-VDD18_VCO_SXR)") (class "Default")
      (node (ref "C112") (pin "1") (pinfunction "1_1") (pintype "passive"))
      (node (ref "L40") (pin "1") (pinfunction "1_1") (pintype "passive"))
      (node (ref "U2") (pin "AK22") (pinfunction "VDD18_VCO_SXR_AK22") (pintype "passive"))
    )
    (net (code "65") (name "Net-(U2B-VDD18_VCO_SXT)") (class "Default")
      (node (ref "C95") (pin "2") (pinfunction "2_2") (pintype "passive"))
      (node (ref "L32") (pin "2") (pinfunction "2_2") (pintype "passive"))
      (node (ref "U2") (pin "G3") (pinfunction "VDD18_VCO_SXT_G3") (pintype "passive"))
    )
    (net (code "66") (name "Net-(U2B-VDDO_TL0BUF_TRF)") (class "Default")
      (node (ref "C116") (pin "1") (pinfunction "1_1") (pintype "passive"))
      (node (ref "L41") (pin "1") (pinfunction "1_1") (pintype "passive"))
      (node (ref "U2") (pin "D6") (pinfunction "VDDO_TL0BUF_TRF_D6") (pintype "passive"))
      (node (ref "U2") (pin "F8") (pinfunction "VDD_TL0BUF_TRF_F8") (pintype "passive"))
    )
    (net (code "67") (name "Net-(U2B-VDD_AFE)") (class "Default")
      (node (ref "C109") (pin "1") (pinfunction "1_1") (pintype "passive"))
      (node (ref "L50") (pin "1") (pinfunction "1_1") (pintype "passive"))
      (node (ref "U2") (pin "AJ25") (pinfunction "VDD_AFE_AJ25") (pintype "passive"))
    )
    (net (code "68") (name "Net-(U2B-VDD_CP_CGEN)") (class "Default")
      (node (ref "C102") (pin "1") (pinfunction "1_1") (pintype "passive"))
      (node (ref "L73") (pin "1") (pinfunction "1_1") (pintype "passive"))
      (node (ref "U2") (pin "F20") (pinfunction "VDD_CP_CGEN_F20") (pintype "passive"))
    )
    (net (code "69") (name "Net-(U2B-VDD_CP_SXR)") (class "Default")
      (node (ref "C106") (pin "1") (pinfunction "1_1") (pintype "passive"))
      (node (ref "U2") (pin "AL19") (pinfunction "VDD_CP_SXR_AL19") (pintype "passive"))
    )
    (net (code "70") (name "Net-(U2B-VDD_CP_SXT)") (class "Default")
      (node (ref "C88") (pin "2") (pinfunction "2_2") (pintype "passive"))
      (node (ref "U2") (pin "J3") (pinfunction "VDD_CP_SXT_J3") (pintype "passive"))
    )
    (net (code "71") (name "Net-(U2B-VDD_DIV_CGEN)") (class "Default")
      (node (ref "C101") (pin "1") (pinfunction "1_1") (pintype "passive"))
      (node (ref "U2") (pin "E19") (pinfunction "VDD_DIV_CGEN_E19") (pintype "passive"))
    )
    (net (code "72") (name "Net-(U2B-VDD_DIV_SXR)") (class "Default")
      (node (ref "C107") (pin "1") (pinfunction "1_1") (pintype "passive"))
      (node (ref "U2") (pin "AM20") (pinfunction "VDD_DIV_SXR_AM20") (pintype "passive"))
    )
    (net (code "73") (name "Net-(U2B-VDD_MXLOBUF_RFE)") (class "Default")
      (node (ref "C108") (pin "1") (pinfunction "1_1") (pintype "passive"))
      (node (ref "L49") (pin "1") (pinfunction "1_1") (pintype "passive"))
      (node (ref "U2") (pin "AN17") (pinfunction "VDD_MXLOBUF_RFE_AN17") (pintype "passive"))
    )
    (net (code "74") (name "Net-(U2B-VDD_SPI_BUF)") (class "Default")
      (node (ref "C91") (pin "2") (pinfunction "2_2") (pintype "passive"))
      (node (ref "L29") (pin "2") (pinfunction "2_2") (pintype "passive"))
      (node (ref "U2") (pin "F24") (pinfunction "VDD_SPI_BUF_F24") (pintype "passive"))
    )
    (net (code "75") (name "Net-(U2B-VDD_TBB)") (class "Default")
      (node (ref "C82") (pin "2") (pinfunction "2_2") (pintype "passive"))
      (node (ref "L38") (pin "2") (pinfunction "2_2") (pintype "passive"))
      (node (ref "U2") (pin "P4") (pinfunction "VDD_TBB_P4") (pintype "passive"))
    )
    (net (code "76") (name "Net-(U2B-VDD_TPAD_TRF)") (class "Default")
      (node (ref "C99") (pin "1") (pinfunction "1_1") (pintype "passive"))
      (node (ref "U2") (pin "B16") (pinfunction "VDD_TPAD_TRF_B16") (pintype "passive"))
    )
    (net (code "77") (name "Net-(U20-NRST)") (class "Default")
      (node (ref "R64") (pin "2") (pinfunction "2_2") (pintype "passive"))
      (node (ref "U20") (pin "D4") (pinfunction "NRST_D4") (pintype "passive"))
    )
    (net (code "78") (name "Net-(U21-EN1)") (class "Default")
      (node (ref "C54") (pin "2") (pinfunction "2_2") (pintype "passive"))
      (node (ref "L9") (pin "2") (pinfunction "2_2") (pintype "passive"))
      (node (ref "U21") (pin "1") (pinfunction "IN1_1") (pintype "passive"))
      (node (ref "U21") (pin "2") (pinfunction "IN1_2") (pintype "passive"))
      (node (ref "U21") (pin "20") (pinfunction "EN1_20") (pintype "passive"))
    )
    (net (code "79") (name "Net-(U21-EN2)") (class "Default")
      (node (ref "C55") (pin "2") (pinfunction "2_2") (pintype "passive"))
      (node (ref "L10") (pin "2") (pinfunction "2_2") (pintype "passive"))
      (node (ref "U21") (pin "4") (pinfunction "IN2_4") (pintype "passive"))
      (node (ref "U21") (pin "5") (pinfunction "IN2_5") (pintype "passive"))
      (node (ref "U21") (pin "6") (pinfunction "EN2_6") (pintype "passive"))
    )
    (net (code "80") (name "Net-(U21-FB1)") (class "Default")
      (node (ref "R67") (pin "1") (pinfunction "1_1") (pintype "passive"))
      (node (ref "R68") (pin "1") (pinfunction "1_1") (pintype "passive"))
      (node (ref "U21") (pin "16") (pinfunction "FB1_16") (pintype "passive"))
    )
    (net (code "81") (name "Net-(U21-FB2)") (class "Default")
      (node (ref "R69") (pin "1") (pinfunction "1_1") (pintype "passive"))
      (node (ref "R70") (pin "1") (pinfunction "1_1") (pintype "passive"))
      (node (ref "U21") (pin "10") (pinfunction "FB2_10") (pintype "passive"))
    )
    (net (code "82") (name "Net-(U21-NR1)") (class "Default")
      (node (ref "C44") (pin "2") (pinfunction "2_2") (pintype "passive"))
      (node (ref "U21") (pin "19") (pinfunction "NR1_19") (pintype "passive"))
    )
    (net (code "83") (name "Net-(U21-NR2)") (class "Default")
      (node (ref "C60") (pin "2") (pinfunction "2_2") (pintype "passive"))
      (node (ref "U21") (pin "7") (pinfunction "NR2_7") (pintype "passive"))
    )
    (net (code "84") (name "Net-(U22-EN1)") (class "Default")
      (node (ref "C56") (pin "2") (pinfunction "2_2") (pintype "passive"))
      (node (ref "L11") (pin "2") (pinfunction "2_2") (pintype "passive"))
      (node (ref "U22") (pin "1") (pinfunction "IN1_1") (pintype "passive"))
      (node (ref "U22") (pin "2") (pinfunction "IN1_2") (pintype "passive"))
      (node (ref "U22") (pin "20") (pinfunction "EN1_20") (pintype "passive"))
    )
    (net (code "85") (name "Net-(U22-EN2)") (class "Default")
      (node (ref "C57") (pin "2") (pinfunction "2_2") (pintype "passive"))
      (node (ref "L12") (pin "2") (pinfunction "2_2") (pintype "passive"))
      (node (ref "U22") (pin "4") (pinfunction "IN2_4") (pintype "passive"))
      (node (ref "U22") (pin "5") (pinfunction "IN2_5") (pintype "passive"))
      (node (ref "U22") (pin "6") (pinfunction "EN2_6") (pintype "passive"))
    )
    (net (code "86") (name "Net-(U22-FB1)") (class "Default")
      (node (ref "R71") (pin "1") (pinfunction "1_1") (pintype "passive"))
      (node (ref "R72") (pin "1") (pinfunction "1_1") (pintype "passive"))
      (node (ref "U22") (pin "16") (pinfunction "FB1_16") (pintype "passive"))
    )
    (net (code "87") (name "Net-(U22-FB2)") (class "Default")
      (node (ref "R73") (pin "1") (pinfunction "1_1") (pintype "passive"))
      (node (ref "R74") (pin "1") (pinfunction "1_1") (pintype "passive"))
      (node (ref "U22") (pin "10") (pinfunction "FB2_10") (pintype "passive"))
    )
    (net (code "88") (name "Net-(U22-NR1)") (class "Default")
      (node (ref "C45") (pin "2") (pinfunction "2_2") (pintype "passive"))
      (node (ref "U22") (pin "19") (pinfunction "NR1_19") (pintype "passive"))
    )
    (net (code "89") (name "Net-(U22-NR2)") (class "Default")
      (node (ref "C61") (pin "2") (pinfunction "2_2") (pintype "passive"))
      (node (ref "U22") (pin "7") (pinfunction "NR2_7") (pintype "passive"))
    )
    (net (code "90") (name "Net-(U28-OUT)") (class "Default")
      (node (ref "C153") (pin "1") (pinfunction "1_1") (pintype "passive"))
      (node (ref "C154") (pin "1") (pinfunction "1_1") (pintype "passive"))
      (node (ref "C155") (pin "1") (pinfunction "1_1") (pintype "passive"))
      (node (ref "C156") (pin "1") (pinfunction "1_1") (pintype "passive"))
      (node (ref "C157") (pin "1") (pinfunction "1_1") (pintype "passive"))
      (node (ref "C158") (pin "1") (pinfunction "1_1") (pintype "passive"))
      (node (ref "C159") (pin "1") (pinfunction "1_1") (pintype "passive"))
      (node (ref "U1") (pin "H3") (pinfunction "VCCO_35_H3") (pintype "power_in"))
      (node (ref "U1") (pin "J7") (pinfunction "VCCO_35_J7") (pintype "power_in"))
      (node (ref "U1") (pin "K1") (pinfunction "VCCO_35_K1") (pintype "power_in"))
      (node (ref "U1") (pin "K7") (pinfunction "VCCO_35_K7") (pintype "power_in"))
      (node (ref "U1") (pin "L7") (pinfunction "VCCO_35_L7") (pintype "power_in"))
      (node (ref "U1") (pin "M7") (pinfunction "VCCO_35_M7") (pintype "power_in"))
      (node (ref "U28") (pin "A2") (pinfunction "OUT_A2") (pintype "passive"))
      (node (ref "U29") (pin "A2") (pinfunction "OUT_A2") (pintype "passive"))
    )
    (net (code "91") (name "Net-(U29-VDD)") (class "Default")
      (node (ref "L54") (pin "2") (pinfunction "2_2") (pintype "passive"))
      (node (ref "U29") (pin "A1") (pinfunction "VDD_A1") (pintype "passive"))
    )
    (net (code "92") (name "unconnected-(U19-nINT-PadD2)") (class "Default")
      (node (ref "U19") (pin "D2") (pinfunction "nINT_D2") (pintype "passive+no_connect"))
    )
    (net (code "93") (name "unconnected-(U20-nINT-PadD2)") (class "Default")
      (node (ref "U20") (pin "D2") (pinfunction "nINT_D2") (pintype "passive+no_connect"))
    )
    (net (code "94") (name "unconnected-(U21-PG1-Pad17)") (class "Default")
      (node (ref "U21") (pin "17") (pinfunction "PG1_17") (pintype "passive+no_connect"))
    )
    (net (code "95") (name "unconnected-(U21-PG2-Pad9)") (class "Default")
      (node (ref "U21") (pin "9") (pinfunction "PG2_9") (pintype "passive+no_connect"))
    )
    (net (code "96") (name "unconnected-(U22-PG1-Pad17)") (class "Default")
      (node (ref "U22") (pin "17") (pinfunction "PG1_17") (pintype "passive+no_connect"))
    )
    (net (code "97") (name "unconnected-(U22-PG2-Pad9)") (class "Default")
      (node (ref "U22") (pin "9") (pinfunction "PG2_9") (pintype "passive+no_connect"))
    )
  )
)
